# Robot.net
KiCad netlist of a schematic drawn in EAGLE
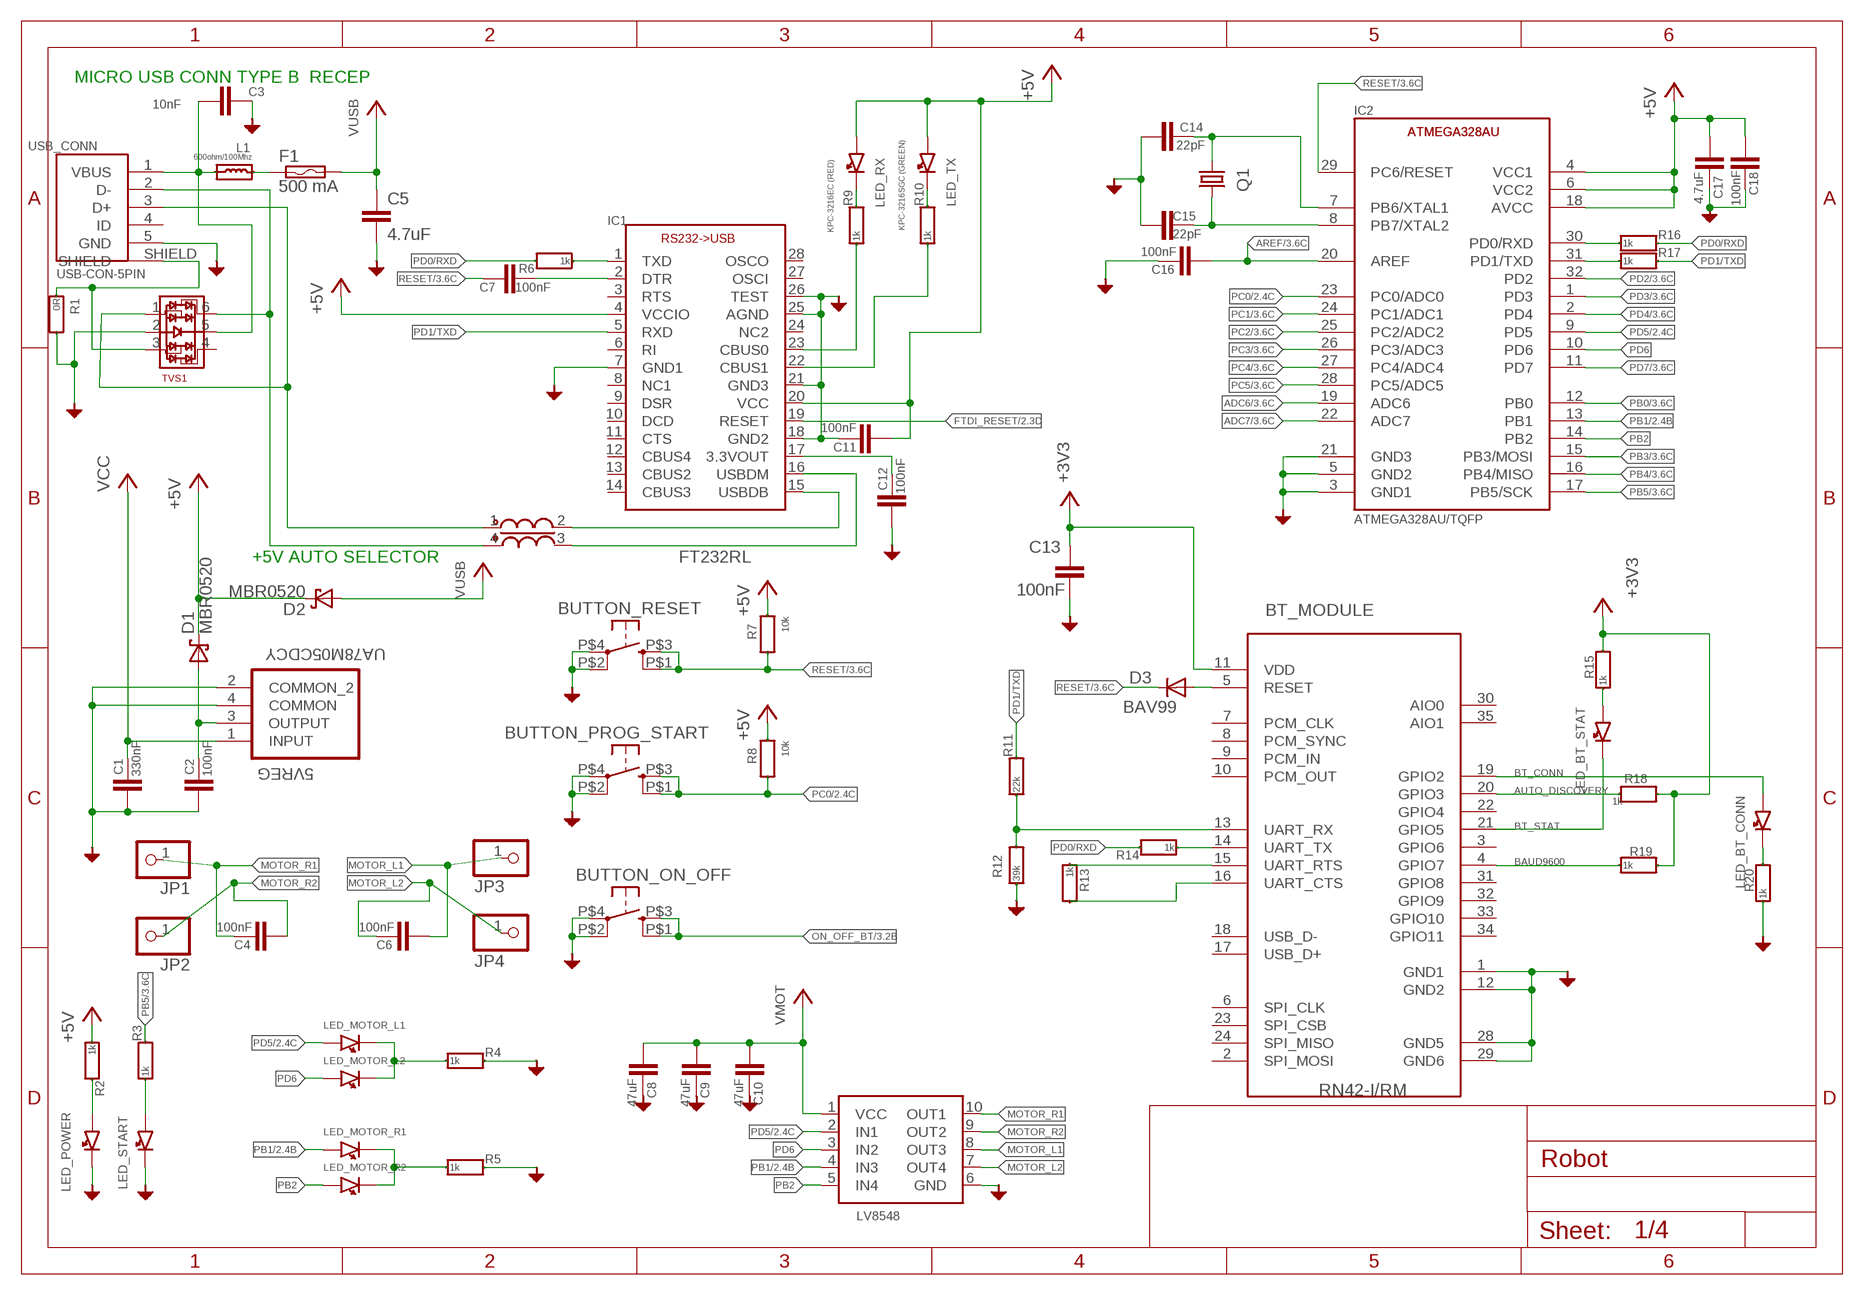
[diagram p0: schematic, sheet 1]
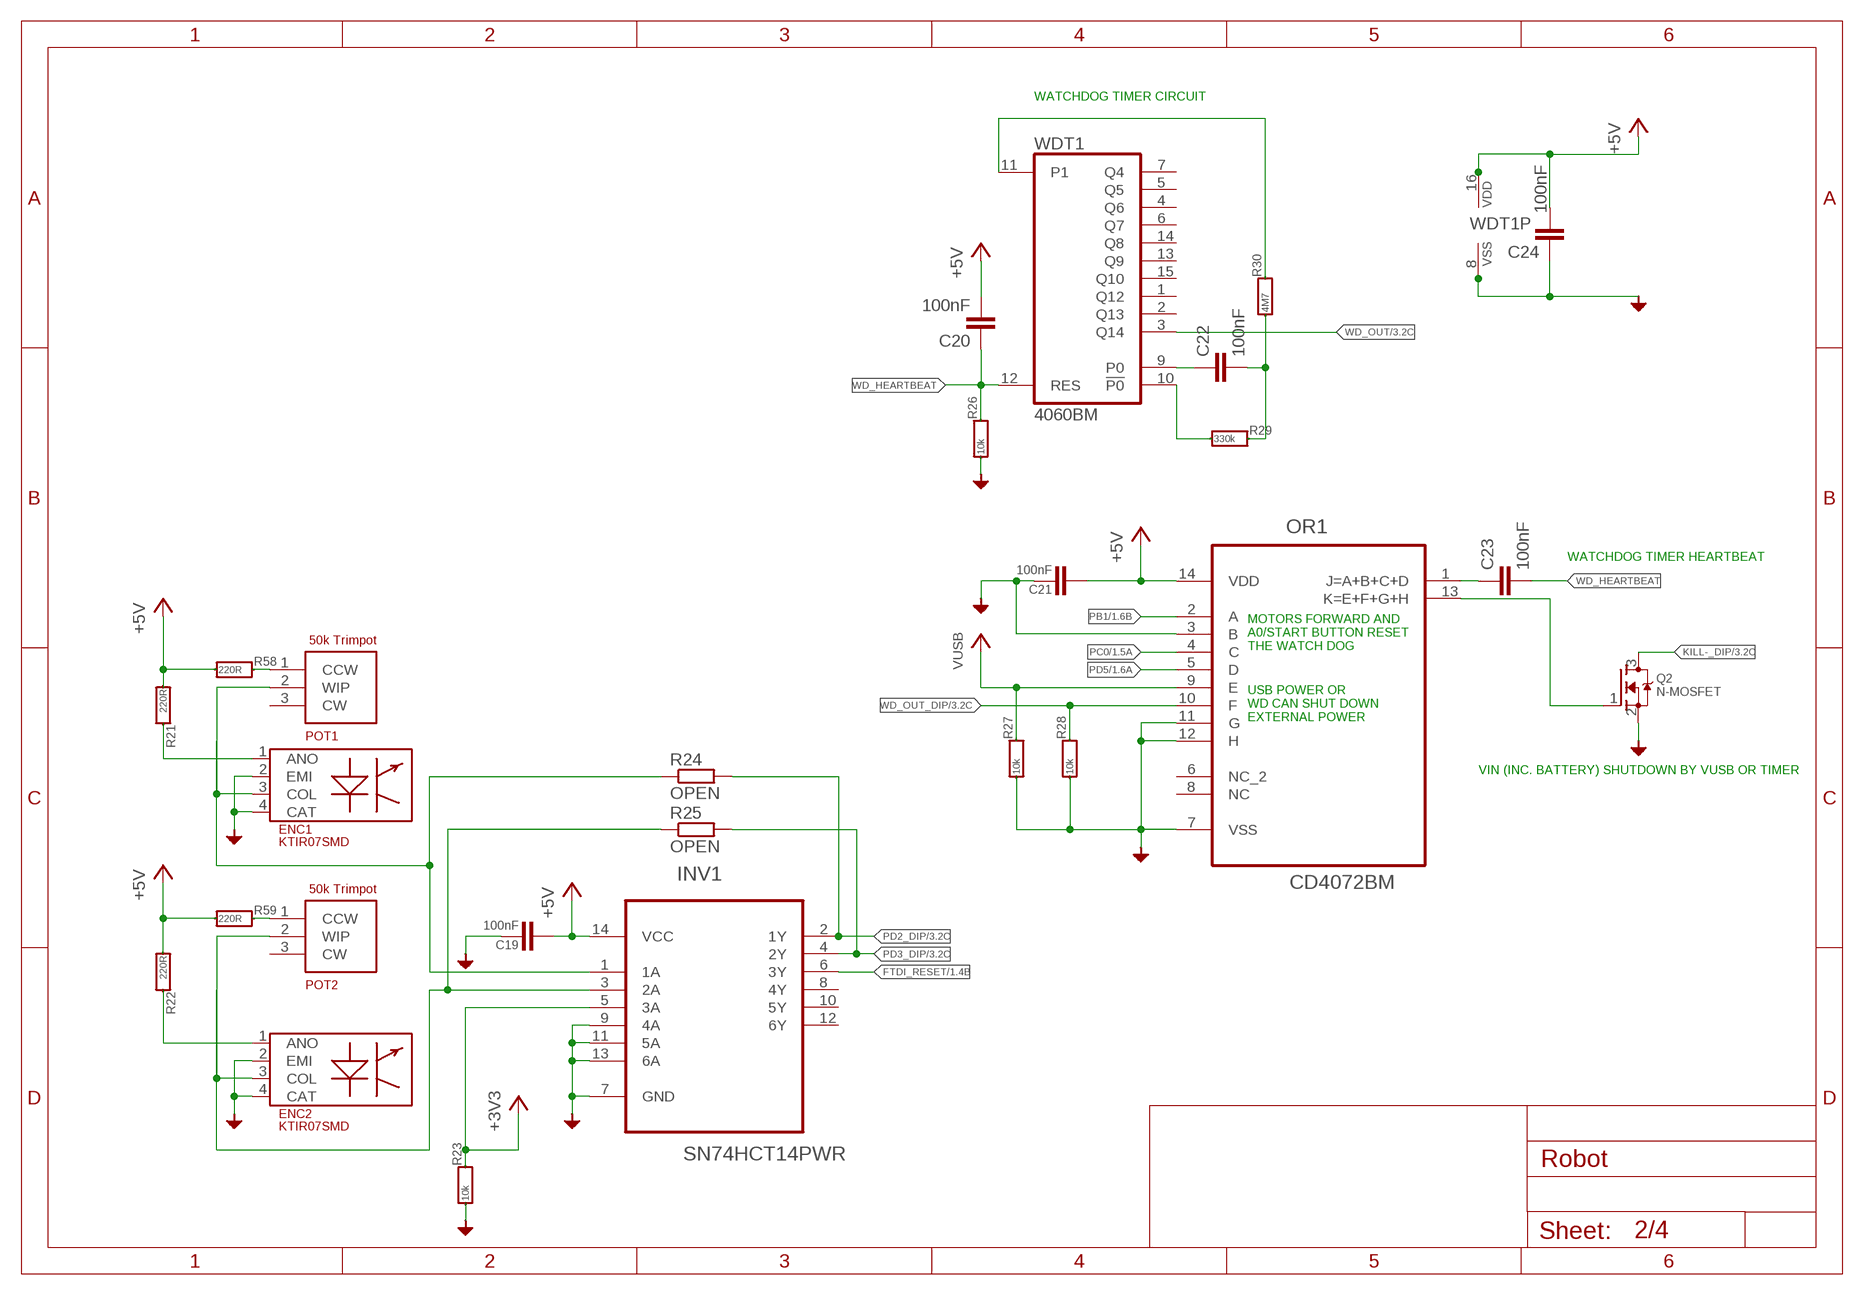
[diagram p1: schematic, sheet 2]
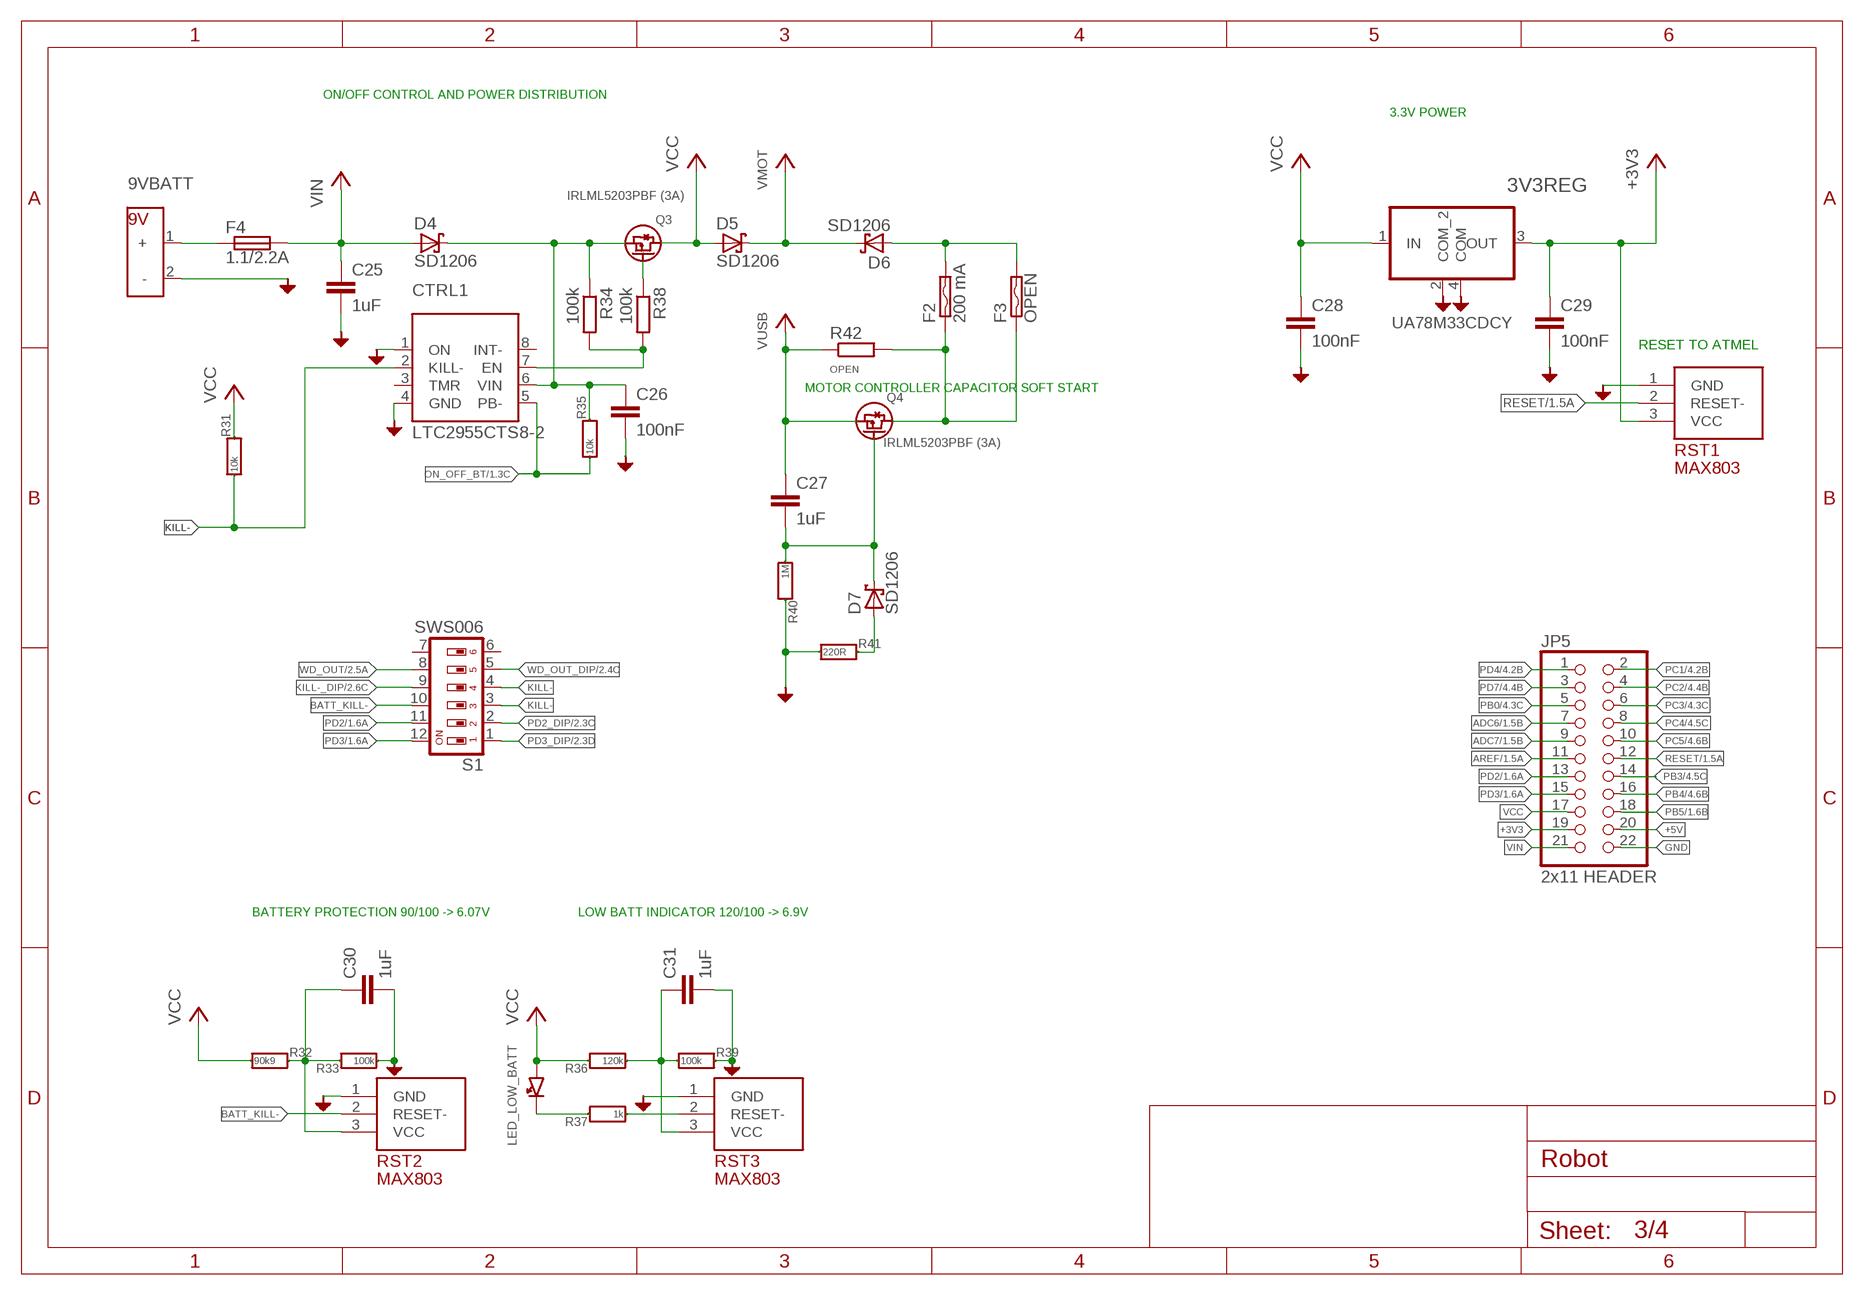
[diagram p2: schematic, sheet 3]
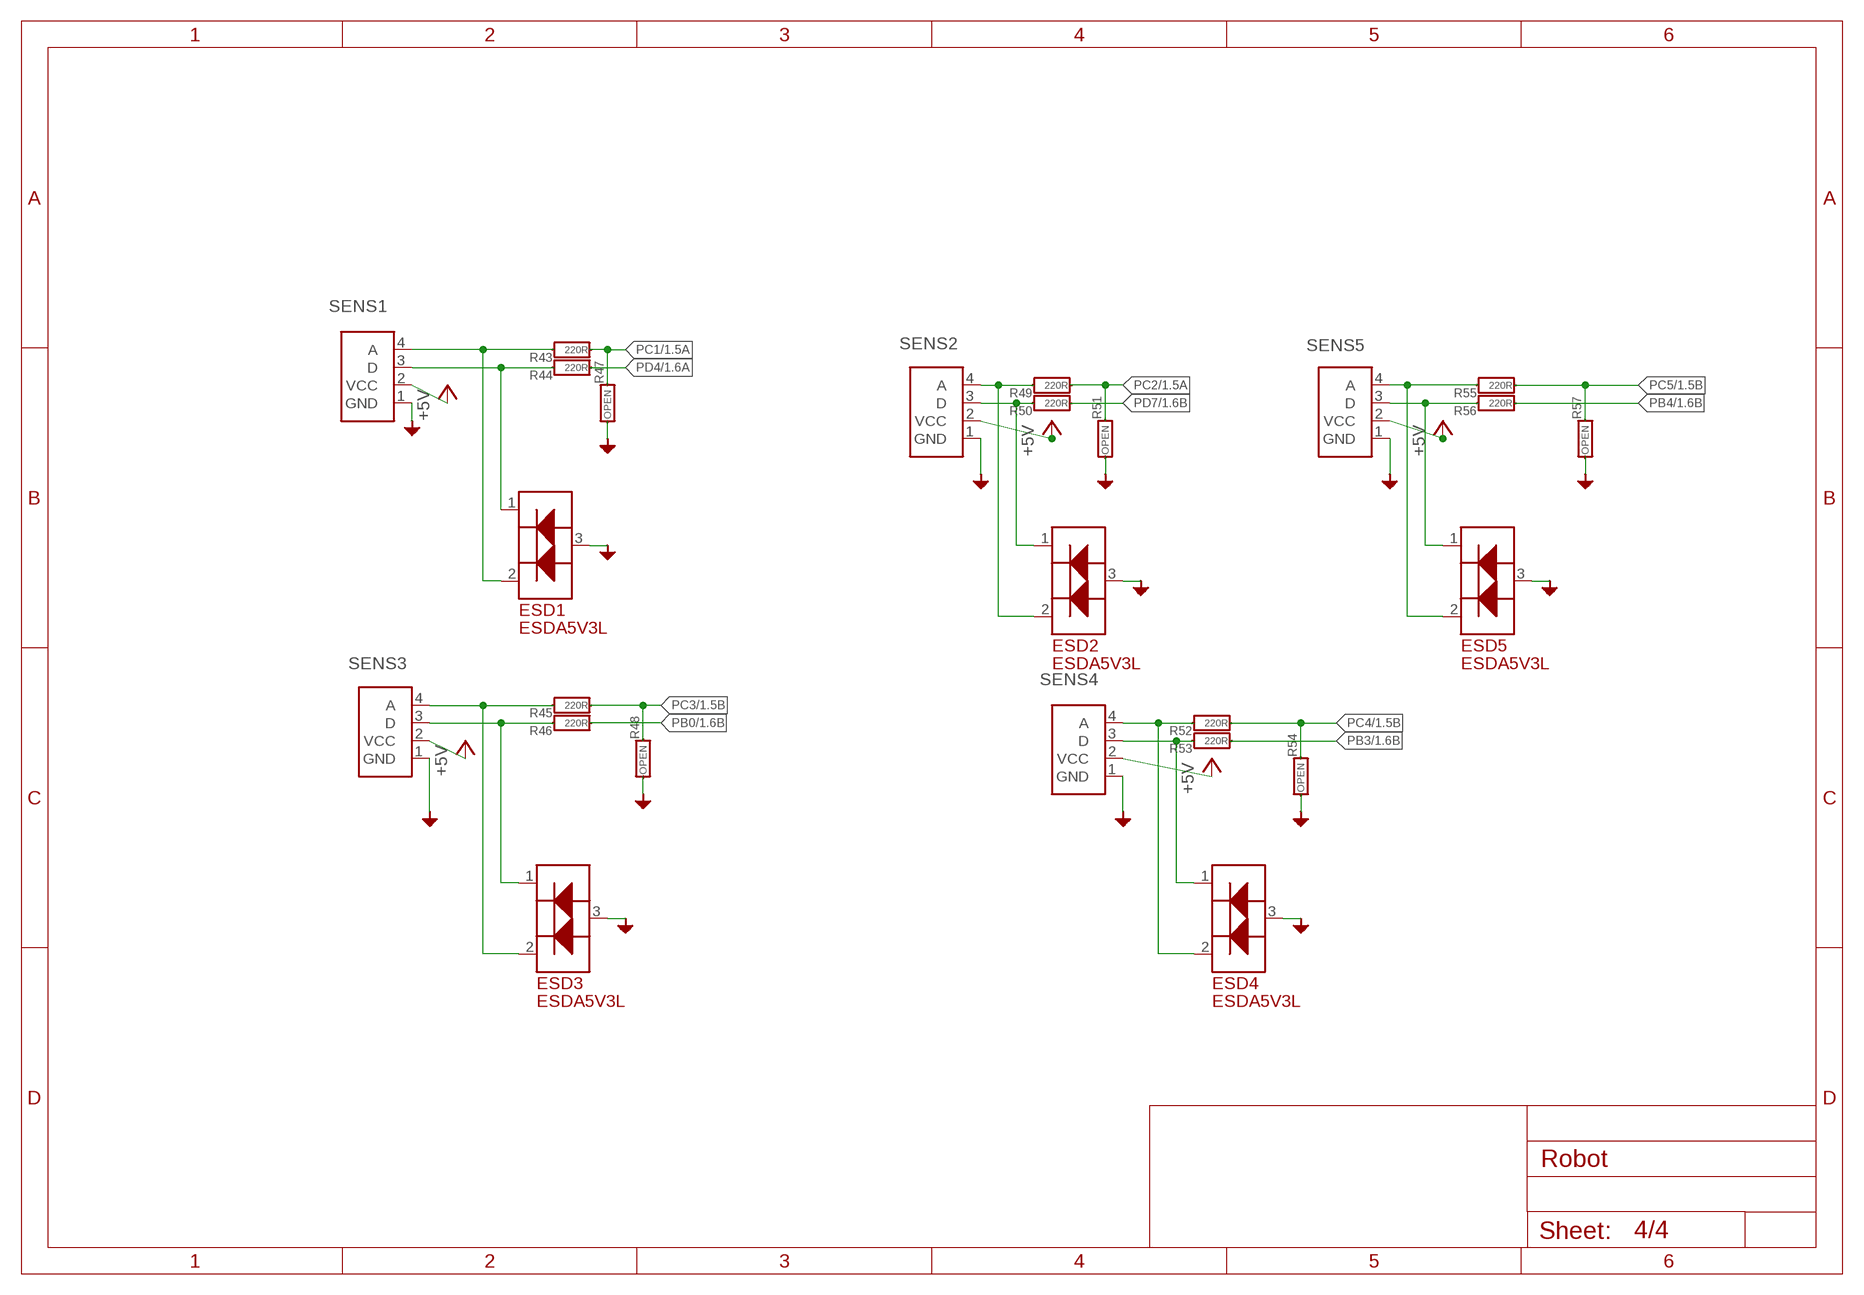
[diagram p3: schematic, sheet 4]

(export (version "E")
  (design (tool "Eeschema 10.0.6"))
  (components
    (comp (ref "C19")
      (value "100nF")
      (footprint "eagle-import:C0805")
      (fields (field (name "MF") "AVX") (field (name "MPN") "08055C104KAT2A"))
      (libsource (lib "eagle-import") (part "C-EUC0805"))
    )
    (comp (ref "C20")
      (value "100nF")
      (footprint "eagle-import:C0805")
      (fields (field (name "MF") "AVX") (field (name "MPN") "08055C104KAT2A"))
      (libsource (lib "eagle-import") (part "C-EUC0805"))
    )
    (comp (ref "C21")
      (value "100nF")
      (footprint "eagle-import:C0805")
      (fields (field (name "MF") "AVX") (field (name "MPN") "08055C104KAT2A"))
      (libsource (lib "eagle-import") (part "C-EUC0805"))
    )
    (comp (ref "C22")
      (value "100nF")
      (footprint "eagle-import:C0805")
      (fields (field (name "MF") "AVX") (field (name "MPN") "08055C104KAT2A"))
      (libsource (lib "eagle-import") (part "C-EUC0805"))
    )
    (comp (ref "C23")
      (value "100nF")
      (footprint "eagle-import:C0805")
      (fields (field (name "MF") "AVX") (field (name "MPN") "08055C104KAT2A"))
      (libsource (lib "eagle-import") (part "C-EUC0805"))
    )
    (comp (ref "C24")
      (value "100nF")
      (footprint "eagle-import:C0805")
      (fields (field (name "MF") "AVX") (field (name "MPN") "08055C104KAT2A"))
      (libsource (lib "eagle-import") (part "C-EUC0805"))
    )
    (comp (ref "ENC1")
      (value "KTIR07SMD")
      (footprint "eagle-import:KTIR07")
      (fields (field (name "MF") "KINGBRIGHT") (field (name "MPN") "KTIR0711S"))
      (libsource (lib "eagle-import") (part "KTIR07SMD"))
    )
    (comp (ref "ENC2")
      (value "KTIR07SMD")
      (footprint "eagle-import:KTIR07")
      (fields (field (name "MF") "KINGBRIGHT") (field (name "MPN") "KTIR0711S"))
      (libsource (lib "eagle-import") (part "KTIR07SMD"))
    )
    (comp (ref "INV1")
      (value "SN74HCT14PWR")
      (footprint "eagle-import:SOP65P640X120-14N")
      (fields
        (field (name "MF") "NXP")
        (field (name "MPN") "74HCT14PW,118")
        (field (name "OC_FARNELL") "2438727")
      )
      (libsource (lib "eagle-import") (part "SN74HCT14PWR"))
    )
    (comp (ref "OR1")
      (value "CD4072BM")
      (footprint "eagle-import:SOIC127P600X175-14N")
      (fields (field (name "MF") "TEXAS INSTRUMENTS"))
      (libsource (lib "eagle-import") (part "CD4072BM"))
    )
    (comp (ref "POT1")
      (value "TC33-TRIMPOT")
      (footprint "eagle-import:TC33-TRIMPOT")
      (fields (field (name "MF") "BOURNS") (field (name "MPN") "TC33X-2-503E"))
      (libsource (lib "eagle-import") (part "TC33-TRIMPOT"))
    )
    (comp (ref "POT2")
      (value "TC33-TRIMPOT")
      (footprint "eagle-import:TC33-TRIMPOT")
      (fields (field (name "MF") "BOURNS") (field (name "MPN") "TC33X-2-503E"))
      (libsource (lib "eagle-import") (part "TC33-TRIMPOT"))
    )
    (comp (ref "Q2")
      (value "N-MOSFET")
      (footprint "eagle-import:SOT23")
      (fields (field (name "MF") "FAIRCHILD SEMICONDUCTOR") (field (name "MPN") "FDV301N"))
      (libsource (lib "eagle-import") (part "MOSFET-NREFLOW"))
    )
    (comp (ref "R21")
      (value "220R")
      (footprint "eagle-import:R0805")
      (fields (field (name "MF") "MULTICOMP") (field (name "MPN") "MCWR08X2200FTL"))
      (libsource (lib "eagle-import") (part "MYRES_0805"))
    )
    (comp (ref "R22")
      (value "220R")
      (footprint "eagle-import:R0805")
      (fields (field (name "MF") "MULTICOMP") (field (name "MPN") "MCWR08X2200FTL"))
      (libsource (lib "eagle-import") (part "MYRES_0805"))
    )
    (comp (ref "R23")
      (value "10k")
      (footprint "eagle-import:R0805")
      (fields (field (name "MF") "YAGEO (PHYCOMP)") (field (name "MPN") "RC0805FR-0710KL"))
      (libsource (lib "eagle-import") (part "MYRES_0805"))
    )
    (comp (ref "R24")
      (value "OPEN")
      (footprint "eagle-import:R0805")
      (libsource (lib "eagle-import") (part "R-EU_R0805"))
    )
    (comp (ref "R25")
      (value "OPEN")
      (footprint "eagle-import:R0805")
      (libsource (lib "eagle-import") (part "R-EU_R0805"))
    )
    (comp (ref "R26")
      (value "10k")
      (footprint "eagle-import:R0805")
      (fields (field (name "MF") "YAGEO (PHYCOMP)") (field (name "MPN") "RC0805FR-0710KL"))
      (libsource (lib "eagle-import") (part "MYRES_0805"))
    )
    (comp (ref "R27")
      (value "10k")
      (footprint "eagle-import:R0805")
      (fields (field (name "MF") "YAGEO (PHYCOMP)") (field (name "MPN") "RC0805FR-0710KL"))
      (libsource (lib "eagle-import") (part "MYRES_0805"))
    )
    (comp (ref "R28")
      (value "10k")
      (footprint "eagle-import:R0805")
      (fields (field (name "MF") "YAGEO (PHYCOMP)") (field (name "MPN") "RC0805FR-0710KL"))
      (libsource (lib "eagle-import") (part "MYRES_0805"))
    )
    (comp (ref "R29")
      (value "330k")
      (footprint "eagle-import:R0805")
      (fields (field (name "MF") "VISHAY DRALORIC") (field (name "MPN") "CRCW0805330KFKEA"))
      (libsource (lib "eagle-import") (part "MYRES_0805"))
    )
    (comp (ref "R30")
      (value "4M7")
      (footprint "eagle-import:R0805")
      (fields (field (name "MF") "VISHAY DRALORIC") (field (name "MPN") "RCV08054M70FKEA"))
      (libsource (lib "eagle-import") (part "MYRES_0805"))
    )
    (comp (ref "R58")
      (value "220R")
      (footprint "eagle-import:R0805")
      (fields (field (name "MF") "MULTICOMP") (field (name "MPN") "MCWR08X2200FTL"))
      (libsource (lib "eagle-import") (part "MYRES_0805"))
    )
    (comp (ref "R59")
      (value "220R")
      (footprint "eagle-import:R0805")
      (fields (field (name "MF") "MULTICOMP") (field (name "MPN") "MCWR08X2200FTL"))
      (libsource (lib "eagle-import") (part "MYRES_0805"))
    )
    (comp (ref "WDT1")
      (value "4060BM")
      (footprint "eagle-import:SO16")
      (fields
        (field (name "MF") "TEXAS INSTRUMENTS")
        (field (name "MPN") "CD4060BM")
        (field (name "OC_FARNELL") "1741260")
      )
      (libsource (lib "eagle-import") (part "4060D"))
    )
    (comp (ref "5VREG")
      (value "UA78M05CDCY")
      (footprint "eagle-import:SOT230P700X180-4N")
      (fields (field (name "MF") "TEXAS INSTRUMENTS") (field (name "OC_FARNELL") "2296030"))
      (libsource (lib "eagle-import") (part "UA78M05CDCY"))
    )
    (comp (ref "BT_MODULE")
      (value "RN42-I/RM")
      (footprint "eagle-import:RN42")
      (fields (field (name "MF") "MICROCHIP"))
      (libsource (lib "eagle-import") (part "BLUETOOTH-RN42{dblquote}"))
    )
    (comp (ref "BUTTON_ON_OFF")
      (value "KSC921J")
      (footprint "eagle-import:TACT_SWITCH_4_PIN")
      (fields (field (name "MF") "C & K COMPONENTS") (field (name "MPN") "KSC921J LFS"))
      (libsource (lib "eagle-import") (part "KSC921J"))
    )
    (comp (ref "BUTTON_PROG_START")
      (value "KSC921J")
      (footprint "eagle-import:TACT_SWITCH_4_PIN")
      (fields (field (name "MF") "C & K COMPONENTS") (field (name "MPN") "KSC921J LFS"))
      (libsource (lib "eagle-import") (part "KSC921J"))
    )
    (comp (ref "BUTTON_RESET")
      (value "KSC921J")
      (footprint "eagle-import:TACT_SWITCH_4_PIN")
      (fields (field (name "MF") "C & K COMPONENTS") (field (name "MPN") "KSC921J LFS"))
      (libsource (lib "eagle-import") (part "KSC921J"))
    )
    (comp (ref "C1")
      (value "330nF")
      (footprint "eagle-import:C0805")
      (fields (field (name "MF") "AVX") (field (name "MPN") "08053C334KAT2A"))
      (libsource (lib "eagle-import") (part "C-EUC0805"))
    )
    (comp (ref "C2")
      (value "100nF")
      (footprint "eagle-import:C0805")
      (fields (field (name "MF") "AVX") (field (name "MPN") "08055C104KAT2A"))
      (libsource (lib "eagle-import") (part "C-EUC0805"))
    )
    (comp (ref "C3")
      (value "10nF")
      (footprint "eagle-import:C0805")
      (fields (field (name "MF") "MULTICOMP") (field (name "MPN") "MC0805B103K500CT"))
      (libsource (lib "eagle-import") (part "C-EUC0805"))
    )
    (comp (ref "C4")
      (value "100nF")
      (footprint "eagle-import:C0805")
      (fields (field (name "MF") "AVX") (field (name "MPN") "08055C104KAT2A"))
      (libsource (lib "eagle-import") (part "C-EUC0805"))
    )
    (comp (ref "C5")
      (value "4.7uF")
      (footprint "eagle-import:C0805")
      (fields (field (name "MF") "MURATA") (field (name "MPN") "GRM21BR61E475KA12L"))
      (libsource (lib "eagle-import") (part "C-EUC0805"))
    )
    (comp (ref "C6")
      (value "100nF")
      (footprint "eagle-import:C0805")
      (fields (field (name "MF") "AVX") (field (name "MPN") "08055C104KAT2A"))
      (libsource (lib "eagle-import") (part "C-EUC0805"))
    )
    (comp (ref "C7")
      (value "100nF")
      (footprint "eagle-import:C0805")
      (fields (field (name "MF") "AVX") (field (name "MPN") "08055C104KAT2A"))
      (libsource (lib "eagle-import") (part "C-EUC0805"))
    )
    (comp (ref "C8")
      (value "47uF")
      (footprint "eagle-import:C1210")
      (fields (field (name "MF") "MURATA") (field (name "MPN") "GRM32EC81C476KE15L"))
      (libsource (lib "eagle-import") (part "C-EUC1210"))
    )
    (comp (ref "C9")
      (value "47uF")
      (footprint "eagle-import:C1210")
      (fields (field (name "MF") "MURATA") (field (name "MPN") "GRM32EC81C476KE15L"))
      (libsource (lib "eagle-import") (part "C-EUC1210"))
    )
    (comp (ref "C10")
      (value "47uF")
      (footprint "eagle-import:C1210")
      (fields (field (name "MF") "MURATA") (field (name "MPN") "GRM32EC81C476KE15L"))
      (libsource (lib "eagle-import") (part "C-EUC1210"))
    )
    (comp (ref "C11")
      (value "100nF")
      (footprint "eagle-import:C0805")
      (fields (field (name "MF") "AVX") (field (name "MPN") "08055C104KAT2A"))
      (libsource (lib "eagle-import") (part "C-EUC0805"))
    )
    (comp (ref "C12")
      (value "100nF")
      (footprint "eagle-import:C0805")
      (fields (field (name "MF") "AVX") (field (name "MPN") "08055C104KAT2A"))
      (libsource (lib "eagle-import") (part "C-EUC0805"))
    )
    (comp (ref "C13")
      (value "100nF")
      (footprint "eagle-import:C0805")
      (fields (field (name "MF") "AVX") (field (name "MPN") "08055C104KAT2A"))
      (libsource (lib "eagle-import") (part "resistor_C-EUC0805"))
    )
    (comp (ref "C14")
      (value "22pF")
      (footprint "eagle-import:C0805")
      (fields (field (name "MF") "YAGEO (PHYCOMP)") (field (name "MPN") "CC0805JRNPO9BN220"))
      (libsource (lib "eagle-import") (part "C-EUC0805"))
    )
    (comp (ref "C15")
      (value "22pF")
      (footprint "eagle-import:C0805")
      (fields (field (name "MF") "YAGEO (PHYCOMP)") (field (name "MPN") "CC0805JRNPO9BN220"))
      (libsource (lib "eagle-import") (part "C-EUC0805"))
    )
    (comp (ref "C16")
      (value "100nF")
      (footprint "eagle-import:C0805")
      (fields (field (name "MF") "AVX") (field (name "MPN") "08055C104KAT2A"))
      (libsource (lib "eagle-import") (part "C-EUC0805"))
    )
    (comp (ref "C17")
      (value "4.7uF")
      (footprint "eagle-import:C0805")
      (fields (field (name "MF") "MURATA") (field (name "MPN") "GRM21BR61E475KA12L"))
      (libsource (lib "eagle-import") (part "C-EUC0805"))
    )
    (comp (ref "C18")
      (value "100nF")
      (footprint "eagle-import:C0805")
      (fields (field (name "MF") "AVX") (field (name "MPN") "08055C104KAT2A"))
      (libsource (lib "eagle-import") (part "C-EUC0805"))
    )
    (comp (ref "D1")
      (value "MBR0520")
      (footprint "eagle-import:SOD123")
      (fields (field (name "MF") "FAIRCHILD SEMICONDUCTOR") (field (name "MPN") "MBR0520L"))
      (libsource (lib "eagle-import") (part "MBR0520"))
    )
    (comp (ref "D2")
      (value "MBR0520")
      (footprint "eagle-import:SOD123")
      (fields (field (name "MF") "FAIRCHILD SEMICONDUCTOR") (field (name "MPN") "MBR0520L"))
      (libsource (lib "eagle-import") (part "MBR0520"))
    )
    (comp (ref "D3")
      (value "BAV99")
      (footprint "eagle-import:SOT23")
      (fields (field (name "MF") "MULTICOMP"))
      (libsource (lib "eagle-import") (part "D-A1-C3"))
    )
    (comp (ref "F1")
      (value "500 mA")
      (footprint "eagle-import:PT1206")
      (fields (field (name "MF") "TE CONNECTIVITY / RAYCHEM") (field (name "MPN") "NANOSMDC050F/13.2-2"))
      (libsource (lib "eagle-import") (part "POLYSWITCH"))
    )
    (comp (ref "IC1")
      (value "FT232RL")
      (footprint "eagle-import:SSOP28")
      (fields (field (name "MF") "FTDI") (field (name "MPN") "FT232RL-REEL"))
      (libsource (lib "eagle-import") (part "FT232RL"))
    )
    (comp (ref "IC2")
      (value "ATMEGA328AU/TQFP")
      (footprint "eagle-import:TQFP32-08")
      (fields (field (name "MF") "ATMEL") (field (name "MPN") "ATMEGA328P-AU"))
      (libsource (lib "eagle-import") (part "ATMEGA328AU"))
    )
    (comp (ref "JP1")
      (value "1X01 PIN")
      (footprint "eagle-import:1X01")
      (fields (field (name "MF") "WURTH ELEKTRONIK") (field (name "MPN") "61300111121"))
      (libsource (lib "eagle-import") (part "PINHD-1X1"))
    )
    (comp (ref "JP2")
      (value "1X01 PIN")
      (footprint "eagle-import:1X01")
      (fields (field (name "MF") "WURTH ELEKTRONIK") (field (name "MPN") "61300111121"))
      (libsource (lib "eagle-import") (part "PINHD-1X1"))
    )
    (comp (ref "JP3")
      (value "1X01 PIN")
      (footprint "eagle-import:1X01")
      (fields (field (name "MF") "WURTH ELEKTRONIK") (field (name "MPN") "61300111121"))
      (libsource (lib "eagle-import") (part "PINHD-1X1"))
    )
    (comp (ref "JP4")
      (value "1X01 PIN")
      (footprint "eagle-import:1X01")
      (fields (field (name "MF") "WURTH ELEKTRONIK") (field (name "MPN") "61300111121"))
      (libsource (lib "eagle-import") (part "PINHD-1X1"))
    )
    (comp (ref "L1")
      (value "600ohm/100Mhz")
      (footprint "eagle-import:R0603")
      (fields (field (name "MF") "WURTH ELEKTRONIK") (field (name "MPN") "742792651"))
      (libsource (lib "eagle-import") (part "INDUCTOR_0603_600R"))
    )
    (comp (ref "LED_BT_CONN")
      (value "KPC-3216SGC")
      (footprint "eagle-import:LED3216_PAC")
      (fields (field (name "MF") "KINGBRIGHT"))
      (libsource (lib "eagle-import") (part "SMDLED_3216"))
    )
    (comp (ref "LED_BT_STAT")
      (value "KPC-3216SGC")
      (footprint "eagle-import:LED3216_PAC")
      (fields (field (name "MF") "KINGBRIGHT"))
      (libsource (lib "eagle-import") (part "SMDLED_3216"))
    )
    (comp (ref "LED_MOTOR_L1")
      (value "APT3216QBC/D (BLUE)")
      (footprint "eagle-import:LED3216_PAC")
      (fields
        (field (name "MF") "KINGBRIGHT")
        (field (name "MOUSER_PART_NO") "604-APT3216QBC/D")
        (field (name "MPN") "KP-3216QBC-D")
      )
      (libsource (lib "eagle-import") (part "SMDLED_3216"))
    )
    (comp (ref "LED_MOTOR_L2")
      (value "KPC-3216YC")
      (footprint "eagle-import:LED3216_PAC")
      (fields (field (name "MF") "KINGBRIGHT"))
      (libsource (lib "eagle-import") (part "SMDLED_3216"))
    )
    (comp (ref "LED_MOTOR_R1")
      (value "APT3216QBC/D (BLUE)")
      (footprint "eagle-import:LED3216_PAC")
      (fields
        (field (name "MF") "KINGBRIGHT")
        (field (name "MOUSER_PART_NO") "604-APT3216QBC/D")
        (field (name "MPN") "KP-3216QBC-D")
      )
      (libsource (lib "eagle-import") (part "SMDLED_3216"))
    )
    (comp (ref "LED_MOTOR_R2")
      (value "KPC-3216YC")
      (footprint "eagle-import:LED3216_PAC")
      (fields (field (name "MF") "KINGBRIGHT"))
      (libsource (lib "eagle-import") (part "SMDLED_3216"))
    )
    (comp (ref "LED_POWER")
      (value "KPC-3216SGC (GREEN)")
      (footprint "eagle-import:LED3216_PAC")
      (fields (field (name "MF") "KINGBRIGHT") (field (name "MPN") "KPC-3216SGC"))
      (libsource (lib "eagle-import") (part "SMDLED_3216"))
    )
    (comp (ref "LED_RX")
      (value "KPC-3216EC (RED)")
      (footprint "eagle-import:LED3216_PAC")
      (fields (field (name "MF") "KINGBRIGHT") (field (name "MPN") "KPC-3216EC"))
      (libsource (lib "eagle-import") (part "SMDLED_3216"))
    )
    (comp (ref "LED_START")
      (value "KPC-3216SGC")
      (footprint "eagle-import:LED3216_PAC")
      (fields (field (name "MF") "KINGBRIGHT"))
      (libsource (lib "eagle-import") (part "SMDLED_3216"))
    )
    (comp (ref "LED_TX")
      (value "KPC-3216SGC (GREEN)")
      (footprint "eagle-import:LED3216_PAC")
      (fields (field (name "MF") "KINGBRIGHT") (field (name "MPN") "KPC-3216SGC"))
      (libsource (lib "eagle-import") (part "SMDLED_3216"))
    )
    (comp (ref "MOTOR_CONTROLLER")
      (value "LV8548")
      (footprint "eagle-import:LV8548")
      (fields (field (name "MF") "ON SEMICONDUCTOR") (field (name "MPN") "LV8548MC-AH"))
      (libsource (lib "eagle-import") (part "LV8548"))
    )
    (comp (ref "Q1")
      (value "16MHz")
      (footprint "eagle-import:SM49")
      (fields
        (field (name "MF") "IQD FREQUENCY PRODUCTS")
        (field (name "MPN") "LFXTAL003237")
        (field (name "OC_FARNELL") "9713808")
      )
      (libsource (lib "eagle-import") (part "CRYSTALSM49"))
    )
    (comp (ref "R1")
      (value "0R")
      (footprint "eagle-import:R0805")
      (fields (field (name "MF") "MULTICOMP") (field (name "MPN") "MC01W08050R"))
      (libsource (lib "eagle-import") (part "MYRES_0805"))
    )
    (comp (ref "R2")
      (value "1k")
      (footprint "eagle-import:R0805")
      (fields (field (name "MF") "VISHAY DRALORIC") (field (name "MPN") "CRCW08051K00FKTA"))
      (libsource (lib "eagle-import") (part "MYRES_0805"))
    )
    (comp (ref "R3")
      (value "1k")
      (footprint "eagle-import:R0805")
      (fields (field (name "MF") "VISHAY DRALORIC") (field (name "MPN") "CRCW08051K00FKTA"))
      (libsource (lib "eagle-import") (part "MYRES_0805"))
    )
    (comp (ref "R4")
      (value "1k")
      (footprint "eagle-import:R0805")
      (fields (field (name "MF") "VISHAY DRALORIC") (field (name "MPN") "CRCW08051K00FKTA"))
      (libsource (lib "eagle-import") (part "MYRES_0805"))
    )
    (comp (ref "R5")
      (value "1k")
      (footprint "eagle-import:R0805")
      (fields (field (name "MF") "VISHAY DRALORIC") (field (name "MPN") "CRCW08051K00FKTA"))
      (libsource (lib "eagle-import") (part "MYRES_0805"))
    )
    (comp (ref "R6")
      (value "1k")
      (footprint "eagle-import:R0805")
      (fields (field (name "MF") "VISHAY DRALORIC") (field (name "MPN") "CRCW08051K00FKTA"))
      (libsource (lib "eagle-import") (part "MYRES_0805"))
    )
    (comp (ref "R7")
      (value "10k")
      (footprint "eagle-import:R0805")
      (fields (field (name "MF") "YAGEO (PHYCOMP)") (field (name "MPN") "RC0805FR-0710KL"))
      (libsource (lib "eagle-import") (part "MYRES_0805"))
    )
    (comp (ref "R8")
      (value "10k")
      (footprint "eagle-import:R0805")
      (fields (field (name "MF") "YAGEO (PHYCOMP)") (field (name "MPN") "RC0805FR-0710KL"))
      (libsource (lib "eagle-import") (part "MYRES_0805"))
    )
    (comp (ref "R9")
      (value "1k")
      (footprint "eagle-import:R0805")
      (fields (field (name "MF") "VISHAY DRALORIC") (field (name "MPN") "CRCW08051K00FKTA"))
      (libsource (lib "eagle-import") (part "MYRES_0805"))
    )
    (comp (ref "R10")
      (value "1k")
      (footprint "eagle-import:R0805")
      (fields (field (name "MF") "VISHAY DRALORIC") (field (name "MPN") "CRCW08051K00FKTA"))
      (libsource (lib "eagle-import") (part "MYRES_0805"))
    )
    (comp (ref "R11")
      (value "22k")
      (footprint "eagle-import:R0805")
      (fields (field (name "MF") "WELWYN") (field (name "MPN") "WCR0805-22KFI"))
      (libsource (lib "eagle-import") (part "MYRES_0805"))
    )
    (comp (ref "R12")
      (value "39k")
      (footprint "eagle-import:R0805")
      (fields (field (name "MF") "WELWYN") (field (name "MPN") "WCR0805-39KFI"))
      (libsource (lib "eagle-import") (part "MYRES_0805"))
    )
    (comp (ref "R13")
      (value "1k")
      (footprint "eagle-import:R0805")
      (fields (field (name "MF") "VISHAY DRALORIC") (field (name "MPN") "CRCW08051K00FKTA"))
      (libsource (lib "eagle-import") (part "MYRES_0805"))
    )
    (comp (ref "R14")
      (value "1k")
      (footprint "eagle-import:R0805")
      (fields (field (name "MF") "VISHAY DRALORIC") (field (name "MPN") "CRCW08051K00FKTA"))
      (libsource (lib "eagle-import") (part "MYRES_0805"))
    )
    (comp (ref "R15")
      (value "1k")
      (footprint "eagle-import:R0805")
      (fields (field (name "MF") "VISHAY DRALORIC") (field (name "MPN") "CRCW08051K00FKTA"))
      (libsource (lib "eagle-import") (part "MYRES_0805"))
    )
    (comp (ref "R16")
      (value "1k")
      (footprint "eagle-import:R0805")
      (fields (field (name "MF") "VISHAY DRALORIC") (field (name "MPN") "CRCW08051K00FKTA"))
      (libsource (lib "eagle-import") (part "MYRES_0805"))
    )
    (comp (ref "R17")
      (value "1k")
      (footprint "eagle-import:R0805")
      (fields (field (name "MF") "VISHAY DRALORIC") (field (name "MPN") "CRCW08051K00FKTA"))
      (libsource (lib "eagle-import") (part "MYRES_0805"))
    )
    (comp (ref "R18")
      (value "1k")
      (footprint "eagle-import:R0805")
      (fields (field (name "MF") "VISHAY DRALORIC") (field (name "MPN") "CRCW08051K00FKTA"))
      (libsource (lib "eagle-import") (part "MYRES_0805"))
    )
    (comp (ref "R19")
      (value "1k")
      (footprint "eagle-import:R0805")
      (fields (field (name "MF") "VISHAY DRALORIC") (field (name "MPN") "CRCW08051K00FKTA"))
      (libsource (lib "eagle-import") (part "MYRES_0805"))
    )
    (comp (ref "R20")
      (value "1k")
      (footprint "eagle-import:R0805")
      (fields (field (name "MF") "VISHAY DRALORIC") (field (name "MPN") "CRCW08051K00FKTA"))
      (libsource (lib "eagle-import") (part "MYRES_0805"))
    )
    (comp (ref "TVS1")
      (value "PRTR5V0U4Y")
      (footprint "eagle-import:SOT363")
      (fields (field (name "MF") "NXP") (field (name "MPN") "PRTR5V0U4Y,125"))
      (libsource (lib "eagle-import") (part "PRTR5V0U4Y"))
    )
    (comp (ref "USB_CONN")
      (value "USB-CON-5PIN")
      (footprint "eagle-import:USB-MICRO-MOLEX-105017-0001_V2")
      (fields (field (name "MF") "MOLEX") (field (name "MPN") "105017-0001"))
      (libsource (lib "eagle-import") (part "USB-CON-5PIN"))
    )
    (comp (ref "USB_FILTER")
      (value "SRF3216A")
      (footprint "eagle-import:SRF3216A")
      (fields (field (name "MF") "BOURNS") (field (name "MPN") "SRF3216A-900Y"))
      (libsource (lib "eagle-import") (part "SRF3216A"))
    )
    (comp (ref "ESD1")
      (value "ESDA5V3L")
      (footprint "eagle-import:SOT23")
      (fields (field (name "MF") "STMICROELECTRONICS"))
      (libsource (lib "eagle-import") (part "ESDA5V3L"))
    )
    (comp (ref "ESD2")
      (value "ESDA5V3L")
      (footprint "eagle-import:SOT23")
      (fields (field (name "MF") "STMICROELECTRONICS"))
      (libsource (lib "eagle-import") (part "ESDA5V3L"))
    )
    (comp (ref "ESD3")
      (value "ESDA5V3L")
      (footprint "eagle-import:SOT23")
      (fields (field (name "MF") "STMICROELECTRONICS"))
      (libsource (lib "eagle-import") (part "ESDA5V3L"))
    )
    (comp (ref "ESD4")
      (value "ESDA5V3L")
      (footprint "eagle-import:SOT23")
      (fields (field (name "MF") "STMICROELECTRONICS"))
      (libsource (lib "eagle-import") (part "ESDA5V3L"))
    )
    (comp (ref "ESD5")
      (value "ESDA5V3L")
      (footprint "eagle-import:SOT23")
      (fields (field (name "MF") "STMICROELECTRONICS"))
      (libsource (lib "eagle-import") (part "ESDA5V3L"))
    )
    (comp (ref "R43")
      (value "220R")
      (footprint "eagle-import:R0805")
      (fields (field (name "MF") "MULTICOMP") (field (name "MPN") "MCWR08X2200FTL"))
      (libsource (lib "eagle-import") (part "MYRES_0805"))
    )
    (comp (ref "R44")
      (value "220R")
      (footprint "eagle-import:R0805")
      (fields (field (name "MF") "MULTICOMP") (field (name "MPN") "MCWR08X2200FTL"))
      (libsource (lib "eagle-import") (part "MYRES_0805"))
    )
    (comp (ref "R45")
      (value "220R")
      (footprint "eagle-import:R0805")
      (fields (field (name "MF") "MULTICOMP") (field (name "MPN") "MCWR08X2200FTL"))
      (libsource (lib "eagle-import") (part "MYRES_0805"))
    )
    (comp (ref "R46")
      (value "220R")
      (footprint "eagle-import:R0805")
      (fields (field (name "MF") "MULTICOMP") (field (name "MPN") "MCWR08X2200FTL"))
      (libsource (lib "eagle-import") (part "MYRES_0805"))
    )
    (comp (ref "R47")
      (value "OPEN")
      (footprint "eagle-import:R0805")
      (libsource (lib "eagle-import") (part "MYRES_0805"))
    )
    (comp (ref "R48")
      (value "OPEN")
      (footprint "eagle-import:R0805")
      (libsource (lib "eagle-import") (part "MYRES_0805"))
    )
    (comp (ref "R49")
      (value "220R")
      (footprint "eagle-import:R0805")
      (fields (field (name "MF") "MULTICOMP") (field (name "MPN") "MCWR08X2200FTL"))
      (libsource (lib "eagle-import") (part "MYRES_0805"))
    )
    (comp (ref "R50")
      (value "220R")
      (footprint "eagle-import:R0805")
      (fields (field (name "MF") "MULTICOMP") (field (name "MPN") "MCWR08X2200FTL"))
      (libsource (lib "eagle-import") (part "MYRES_0805"))
    )
    (comp (ref "R51")
      (value "OPEN")
      (footprint "eagle-import:R0805")
      (libsource (lib "eagle-import") (part "MYRES_0805"))
    )
    (comp (ref "R52")
      (value "220R")
      (footprint "eagle-import:R0805")
      (fields (field (name "MF") "MULTICOMP") (field (name "MPN") "MCWR08X2200FTL"))
      (libsource (lib "eagle-import") (part "MYRES_0805"))
    )
    (comp (ref "R53")
      (value "220R")
      (footprint "eagle-import:R0805")
      (fields (field (name "MF") "MULTICOMP") (field (name "MPN") "MCWR08X2200FTL"))
      (libsource (lib "eagle-import") (part "MYRES_0805"))
    )
    (comp (ref "R54")
      (value "OPEN")
      (footprint "eagle-import:R0805")
      (libsource (lib "eagle-import") (part "MYRES_0805"))
    )
    (comp (ref "R55")
      (value "220R")
      (footprint "eagle-import:R0805")
      (fields (field (name "MF") "MULTICOMP") (field (name "MPN") "MCWR08X2200FTL"))
      (libsource (lib "eagle-import") (part "MYRES_0805"))
    )
    (comp (ref "R56")
      (value "220R")
      (footprint "eagle-import:R0805")
      (fields (field (name "MF") "MULTICOMP") (field (name "MPN") "MCWR08X2200FTL"))
      (libsource (lib "eagle-import") (part "MYRES_0805"))
    )
    (comp (ref "R57")
      (value "OPEN")
      (footprint "eagle-import:R0805")
      (libsource (lib "eagle-import") (part "MYRES_0805"))
    )
    (comp (ref "SENS1")
      (value "ROBOT_SENSOR")
      (footprint "eagle-import:ROBOT_SENSOR")
      (libsource (lib "eagle-import") (part "ROBOT_SENSOR"))
    )
    (comp (ref "SENS2")
      (value "ROBOT_SENSOR")
      (footprint "eagle-import:ROBOT_SENSOR")
      (libsource (lib "eagle-import") (part "ROBOT_SENSOR"))
    )
    (comp (ref "SENS3")
      (value "ROBOT_SENSOR")
      (footprint "eagle-import:ROBOT_SENSOR")
      (libsource (lib "eagle-import") (part "ROBOT_SENSOR"))
    )
    (comp (ref "SENS4")
      (value "ROBOT_SENSOR")
      (footprint "eagle-import:ROBOT_SENSOR")
      (libsource (lib "eagle-import") (part "ROBOT_SENSOR"))
    )
    (comp (ref "SENS5")
      (value "ROBOT_SENSOR")
      (footprint "eagle-import:ROBOT_SENSOR")
      (libsource (lib "eagle-import") (part "ROBOT_SENSOR"))
    )
    (comp (ref "3V3REG")
      (value "UA78M33CDCY")
      (footprint "eagle-import:SOT230P700X180-4N")
      (fields (field (name "MF") "TEXAS INSTRUMENTS") (field (name "OC_FARNELL") "2296031"))
      (libsource (lib "eagle-import") (part "UA78M33CDCY"))
    )
    (comp (ref "9VBATT")
      (value "BATTERY_9V")
      (footprint "eagle-import:BATTERY_PAC")
      (fields (field (name "MF") "KEYSTONE") (field (name "MPN") "967"))
      (libsource (lib "eagle-import") (part "BATTERY_9V"))
    )
    (comp (ref "C25")
      (value "1uF")
      (footprint "eagle-import:C0805")
      (fields (field (name "MF") "WALSIN") (field (name "MPN") "0805B104K500CT"))
      (libsource (lib "eagle-import") (part "C-EUC0805"))
    )
    (comp (ref "C26")
      (value "100nF")
      (footprint "eagle-import:C0805")
      (fields (field (name "MF") "AVX") (field (name "MPN") "08055C104KAT2A"))
      (libsource (lib "eagle-import") (part "C-EUC0805"))
    )
    (comp (ref "C27")
      (value "1uF")
      (footprint "eagle-import:C0805")
      (fields (field (name "MF") "WALSIN") (field (name "MPN") "0805B104K500CT"))
      (libsource (lib "eagle-import") (part "C-EUC0805"))
    )
    (comp (ref "C28")
      (value "100nF")
      (footprint "eagle-import:C0805")
      (fields (field (name "MF") "AVX") (field (name "MPN") "08055C104KAT2A"))
      (libsource (lib "eagle-import") (part "C-EUC0805"))
    )
    (comp (ref "C29")
      (value "100nF")
      (footprint "eagle-import:C0805")
      (fields (field (name "MF") "AVX") (field (name "MPN") "08055C104KAT2A"))
      (libsource (lib "eagle-import") (part "C-EUC0805"))
    )
    (comp (ref "C30")
      (value "1uF")
      (footprint "eagle-import:C0805")
      (fields (field (name "MF") "WALSIN") (field (name "MPN") "0805B104K500CT"))
      (libsource (lib "eagle-import") (part "C-EUC0805"))
    )
    (comp (ref "C31")
      (value "1uF")
      (footprint "eagle-import:C0805")
      (fields (field (name "MF") "WALSIN") (field (name "MPN") "0805B104K500CT"))
      (libsource (lib "eagle-import") (part "C-EUC0805"))
    )
    (comp (ref "CTRL1")
      (value "LTC2955CTS8-2")
      (footprint "eagle-import:8TSOT23")
      (fields (field (name "MF") "LINEAR TECHNOLOGY") (field (name "MPN") "LTC2955CTS8-2#TRMPBF"))
      (libsource (lib "eagle-import") (part "LTC2955CTS8-2"))
    )
    (comp (ref "D4")
      (value "SD1206")
      (footprint "eagle-import:SD1206")
      (fields (field (name "MF") "AVX") (field (name "MPN") "SD1206S040S2R0"))
      (libsource (lib "eagle-import") (part "SD1206"))
    )
    (comp (ref "D5")
      (value "SD1206")
      (footprint "eagle-import:SD1206")
      (fields (field (name "MF") "AVX") (field (name "MPN") "SD1206S040S2R0"))
      (libsource (lib "eagle-import") (part "SD1206"))
    )
    (comp (ref "D6")
      (value "SD1206")
      (footprint "eagle-import:SD1206")
      (fields (field (name "MF") "AVX") (field (name "MPN") "SD1206S040S2R0"))
      (libsource (lib "eagle-import") (part "SD1206"))
    )
    (comp (ref "D7")
      (value "SD1206")
      (footprint "eagle-import:SD1206")
      (fields (field (name "MF") "AVX") (field (name "MPN") "SD1206S040S2R0"))
      (libsource (lib "eagle-import") (part "SD1206"))
    )
    (comp (ref "F2")
      (value "200 mA")
      (footprint "eagle-import:PT1206")
      (fields (field (name "MF") "TE CONNECTIVITY / RAYCHEM") (field (name "MPN") "NANOSMDC020F-2"))
      (libsource (lib "eagle-import") (part "POLYSWITCH"))
    )
    (comp (ref "F3")
      (value "OPEN")
      (footprint "eagle-import:PT1206")
      (libsource (lib "eagle-import") (part "POLYSWITCH"))
    )
    (comp (ref "F4")
      (value "1.1/2.2A")
      (footprint "eagle-import:C1812")
      (fields (field (name "MF") "TE CONNECTIVITY / RAYCHEM") (field (name "MPN") "MINISMDC110F/16-2"))
      (libsource (lib "eagle-import") (part "POLYSWITCH_1812C1812"))
    )
    (comp (ref "JP5")
      (value "2x11 HEADER")
      (footprint "eagle-import:2X11")
      (fields (field (name "MF") "MULTICOMP") (field (name "MPN") "2214S-22SG-85"))
      (libsource (lib "eagle-import") (part "PINHD-2X11"))
    )
    (comp (ref "LED_LOW_BATT")
      (value "KPC-3216EC (RED)")
      (footprint "eagle-import:LED3216_PAC")
      (fields (field (name "MF") "KINGBRIGHT") (field (name "MPN") "KPC-3216EC"))
      (libsource (lib "eagle-import") (part "SMDLED_3216"))
    )
    (comp (ref "Q3")
      (value "IRLML5203PBF (3A)")
      (footprint "eagle-import:SOT23")
      (fields (field (name "MF") "INTERNATIONAL RECTIFIER") (field (name "MPN") "IRLML5203PBF"))
      (libsource (lib "eagle-import") (part "PFET"))
    )
    (comp (ref "Q4")
      (value "IRLML5203PBF (3A)")
      (footprint "eagle-import:SOT23")
      (fields (field (name "MF") "INTERNATIONAL RECTIFIER") (field (name "MPN") "IRLML5203PBF"))
      (libsource (lib "eagle-import") (part "PFET"))
    )
    (comp (ref "R31")
      (value "10k")
      (footprint "eagle-import:R0805")
      (fields (field (name "MF") "YAGEO (PHYCOMP)") (field (name "MPN") "RC0805FR-0710KL"))
      (libsource (lib "eagle-import") (part "MYRES_0805"))
    )
    (comp (ref "R32")
      (value "90k9")
      (footprint "eagle-import:R0805")
      (fields (field (name "MF") "MULTICOMP") (field (name "MPN") "MC01W0805190K9"))
      (libsource (lib "eagle-import") (part "MYRES_0805"))
    )
    (comp (ref "R33")
      (value "100k")
      (footprint "eagle-import:R0805")
      (fields (field (name "MF") "YAGEO (PHYCOMP)") (field (name "MPN") "RC0805FR-07100KL"))
      (libsource (lib "eagle-import") (part "MYRES_0805"))
    )
    (comp (ref "R34")
      (value "100k")
      (footprint "eagle-import:R0805")
      (fields (field (name "MF") "YAGEO (PHYCOMP)") (field (name "MPN") "RC0805FR-07100KL"))
      (libsource (lib "eagle-import") (part "R-EU_R0805"))
    )
    (comp (ref "R35")
      (value "10k")
      (footprint "eagle-import:R0805")
      (fields (field (name "MF") "YAGEO (PHYCOMP)") (field (name "MPN") "RC0805FR-0710KL"))
      (libsource (lib "eagle-import") (part "MYRES_0805"))
    )
    (comp (ref "R36")
      (value "120k")
      (footprint "eagle-import:R0805")
      (fields (field (name "MF") "YAGEO (PHYCOMP)") (field (name "MPN") "RC0805FR-07120KL"))
      (libsource (lib "eagle-import") (part "MYRES_0805"))
    )
    (comp (ref "R37")
      (value "1k")
      (footprint "eagle-import:R0805")
      (fields (field (name "MF") "VISHAY DRALORIC") (field (name "MPN") "CRCW08051K00FKTA"))
      (libsource (lib "eagle-import") (part "MYRES_0805"))
    )
    (comp (ref "R38")
      (value "100k")
      (footprint "eagle-import:R0805")
      (fields (field (name "MF") "YAGEO (PHYCOMP)") (field (name "MPN") "RC0805FR-07100KL"))
      (libsource (lib "eagle-import") (part "R-EU_R0805"))
    )
    (comp (ref "R39")
      (value "100k")
      (footprint "eagle-import:R0805")
      (fields (field (name "MF") "YAGEO (PHYCOMP)") (field (name "MPN") "RC0805FR-07100KL"))
      (libsource (lib "eagle-import") (part "MYRES_0805"))
    )
    (comp (ref "R40")
      (value "1M")
      (footprint "eagle-import:R0805")
      (fields (field (name "MF") "VISHAY DALE") (field (name "MPN") "CRCW08051M00FKTB"))
      (libsource (lib "eagle-import") (part "MYRES_0805"))
    )
    (comp (ref "R41")
      (value "220R")
      (footprint "eagle-import:R0805")
      (fields (field (name "MF") "MULTICOMP") (field (name "MPN") "MCWR08X2200FTL"))
      (libsource (lib "eagle-import") (part "MYRES_0805"))
    )
    (comp (ref "R42")
      (value "OPEN")
      (footprint "eagle-import:R0603")
      (libsource (lib "eagle-import") (part "R-EU_R0603"))
    )
    (comp (ref "RST1")
      (value "MAX803SC")
      (footprint "eagle-import:SC70-3L")
      (fields (field (name "MF") "ON SEMICONDUCTOR") (field (name "MPN") "MAX803SQ293T1G"))
      (libsource (lib "eagle-import") (part "MAX803SC"))
    )
    (comp (ref "RST2")
      (value "MAX803SC")
      (footprint "eagle-import:SC70-3L")
      (fields (field (name "MF") "ON SEMICONDUCTOR") (field (name "MPN") "MAX803SQ293T1G"))
      (libsource (lib "eagle-import") (part "MAX803SC"))
    )
    (comp (ref "RST3")
      (value "MAX803SC")
      (footprint "eagle-import:SC70-3L")
      (fields (field (name "MF") "ON SEMICONDUCTOR") (field (name "MPN") "MAX803SQ293T1G"))
      (libsource (lib "eagle-import") (part "MAX803SC"))
    )
    (comp (ref "S1")
      (value "SWS006")
      (footprint "eagle-import:SMS-006")
      (fields (field (name "MF") "MULTICOMP") (field (name "MPN") "MCDM(R)-06-T"))
      (libsource (lib "eagle-import") (part "SWS006"))
    )
  )
  (nets
    (net (code "1") (name "+3V3") (class "Default")
      (node (ref "3V3REG") (pin "3") (pinfunction "OUT_3") (pintype "output"))
      (node (ref "BT_MODULE") (pin "11") (pinfunction "VDD_11") (pintype "bidirectional"))
      (node (ref "C13") (pin "1") (pinfunction "1_1") (pintype "passive"))
      (node (ref "C29") (pin "1") (pinfunction "1_1") (pintype "passive"))
      (node (ref "INV1") (pin "5") (pinfunction "3A_5") (pintype "input"))
      (node (ref "JP5") (pin "19") (pinfunction "19_19") (pintype "passive"))
      (node (ref "R15") (pin "2") (pinfunction "P$2_2") (pintype "bidirectional"))
      (node (ref "R18") (pin "2") (pinfunction "P$2_2") (pintype "bidirectional"))
      (node (ref "R19") (pin "2") (pinfunction "P$2_2") (pintype "bidirectional"))
      (node (ref "R23") (pin "2") (pinfunction "P$2_2") (pintype "bidirectional"))
      (node (ref "RST1") (pin "3") (pinfunction "VCC_3") (pintype "bidirectional"))
    )
    (net (code "2") (name "+5V") (class "Default")
      (node (ref "C11") (pin "2") (pinfunction "2_2") (pintype "passive"))
      (node (ref "C17") (pin "2") (pinfunction "2_2") (pintype "passive"))
      (node (ref "C18") (pin "2") (pinfunction "2_2") (pintype "passive"))
      (node (ref "C19") (pin "2") (pinfunction "2_2") (pintype "passive"))
      (node (ref "C20") (pin "2") (pinfunction "2_2") (pintype "passive"))
      (node (ref "C21") (pin "2") (pinfunction "2_2") (pintype "passive"))
      (node (ref "C24") (pin "2") (pinfunction "2_2") (pintype "passive"))
      (node (ref "D1") (pin "1") (pinfunction "K_1") (pintype "passive"))
      (node (ref "D2") (pin "1") (pinfunction "K_1") (pintype "passive"))
      (node (ref "IC1") (pin "20") (pinfunction "VCC_20") (pintype "bidirectional"))
      (node (ref "IC1") (pin "4") (pinfunction "VCCIO_4") (pintype "bidirectional"))
      (node (ref "IC2") (pin "18") (pinfunction "AVCC_18") (pintype "bidirectional"))
      (node (ref "IC2") (pin "4") (pinfunction "VCC1_4") (pintype "bidirectional"))
      (node (ref "IC2") (pin "6") (pinfunction "VCC2_6") (pintype "bidirectional"))
      (node (ref "INV1") (pin "14") (pinfunction "VCC_14") (pintype "power_in"))
      (node (ref "JP5") (pin "20") (pinfunction "20_20") (pintype "passive"))
      (node (ref "LED_RX") (pin "1") (pinfunction "1_1") (pintype "bidirectional"))
      (node (ref "LED_TX") (pin "1") (pinfunction "1_1") (pintype "bidirectional"))
      (node (ref "OR1") (pin "14") (pinfunction "VDD_14") (pintype "power_in"))
      (node (ref "R2") (pin "1") (pinfunction "P$1_1") (pintype "bidirectional"))
      (node (ref "R21") (pin "1") (pinfunction "P$1_1") (pintype "bidirectional"))
      (node (ref "R22") (pin "1") (pinfunction "P$1_1") (pintype "bidirectional"))
      (node (ref "R58") (pin "1") (pinfunction "P$1_1") (pintype "bidirectional"))
      (node (ref "R59") (pin "1") (pinfunction "P$1_1") (pintype "bidirectional"))
      (node (ref "R7") (pin "2") (pinfunction "P$2_2") (pintype "bidirectional"))
      (node (ref "R8") (pin "2") (pinfunction "P$2_2") (pintype "bidirectional"))
      (node (ref "SENS1") (pin "2") (pinfunction "VCC_2") (pintype "bidirectional"))
      (node (ref "SENS2") (pin "2") (pinfunction "VCC_2") (pintype "bidirectional"))
      (node (ref "SENS3") (pin "2") (pinfunction "VCC_2") (pintype "bidirectional"))
      (node (ref "SENS4") (pin "2") (pinfunction "VCC_2") (pintype "bidirectional"))
      (node (ref "SENS5") (pin "2") (pinfunction "VCC_2") (pintype "bidirectional"))
      (node (ref "WDT1") (pin "16") (pinfunction "VDD_16") (pintype "power_in"))
    )
    (net (code "3") (name "ADC6") (class "Default")
      (node (ref "IC2") (pin "19") (pinfunction "ADC6_19") (pintype "bidirectional"))
      (node (ref "JP5") (pin "7") (pinfunction "7_7") (pintype "passive"))
    )
    (net (code "4") (name "ADC7") (class "Default")
      (node (ref "IC2") (pin "22") (pinfunction "ADC7_22") (pintype "bidirectional"))
      (node (ref "JP5") (pin "9") (pinfunction "9_9") (pintype "passive"))
    )
    (net (code "5") (name "AREF") (class "Default")
      (node (ref "C16") (pin "2") (pinfunction "2_2") (pintype "passive"))
      (node (ref "IC2") (pin "20") (pinfunction "AREF_20") (pintype "bidirectional"))
      (node (ref "JP5") (pin "11") (pinfunction "11_11") (pintype "passive"))
    )
    (net (code "6") (name "AUTO_DISCOVERY") (class "Default")
      (node (ref "BT_MODULE") (pin "20") (pinfunction "GPIO3_20") (pintype "bidirectional"))
      (node (ref "R18") (pin "1") (pinfunction "P$1_1") (pintype "bidirectional"))
    )
    (net (code "7") (name "BATT_KILL-") (class "Default")
      (node (ref "RST2") (pin "2") (pinfunction "RESET-_2") (pintype "bidirectional"))
      (node (ref "S1") (pin "10") (pinfunction "10_10") (pintype "passive"))
    )
    (net (code "8") (name "BAUD9600") (class "Default")
      (node (ref "BT_MODULE") (pin "4") (pinfunction "GPIO7_4") (pintype "bidirectional"))
      (node (ref "R19") (pin "1") (pinfunction "P$1_1") (pintype "bidirectional"))
    )
    (net (code "9") (name "BT_CONN") (class "Default")
      (node (ref "BT_MODULE") (pin "19") (pinfunction "GPIO2_19") (pintype "bidirectional"))
      (node (ref "LED_BT_CONN") (pin "1") (pinfunction "1_1") (pintype "bidirectional"))
    )
    (net (code "10") (name "BT_STAT") (class "Default")
      (node (ref "BT_MODULE") (pin "21") (pinfunction "GPIO5_21") (pintype "bidirectional"))
      (node (ref "LED_BT_STAT") (pin "2") (pinfunction "2_2") (pintype "bidirectional"))
    )
    (net (code "11") (name "FTDI_RESET") (class "Default")
      (node (ref "IC1") (pin "19") (pinfunction "RESET_19") (pintype "bidirectional"))
      (node (ref "INV1") (pin "6") (pinfunction "3Y_6") (pintype "output"))
    )
    (net (code "12") (name "GND") (class "Default")
      (node (ref "3V3REG") (pin "2") (pinfunction "COM_2_2") (pintype "passive"))
      (node (ref "3V3REG") (pin "4") (pinfunction "COM_4") (pintype "passive"))
      (node (ref "5VREG") (pin "2") (pinfunction "COMMON_2_2") (pintype "power_in"))
      (node (ref "5VREG") (pin "4") (pinfunction "COMMON_4") (pintype "power_in"))
      (node (ref "9VBATT") (pin "2") (pinfunction "-_2") (pintype "bidirectional"))
      (node (ref "BT_MODULE") (pin "1") (pinfunction "GND1_1") (pintype "bidirectional"))
      (node (ref "BT_MODULE") (pin "12") (pinfunction "GND2_12") (pintype "bidirectional"))
      (node (ref "BT_MODULE") (pin "28") (pinfunction "GND5_28") (pintype "bidirectional"))
      (node (ref "BT_MODULE") (pin "29") (pinfunction "GND6_29") (pintype "bidirectional"))
      (node (ref "BUTTON_ON_OFF") (pin "P$2") (pinfunction "2_P$2") (pintype "passive"))
      (node (ref "BUTTON_ON_OFF") (pin "P$4") (pinfunction "1_P$4") (pintype "passive"))
      (node (ref "BUTTON_PROG_START") (pin "P$2") (pinfunction "2_P$2") (pintype "passive"))
      (node (ref "BUTTON_PROG_START") (pin "P$4") (pinfunction "1_P$4") (pintype "passive"))
      (node (ref "BUTTON_RESET") (pin "P$2") (pinfunction "2_P$2") (pintype "passive"))
      (node (ref "BUTTON_RESET") (pin "P$4") (pinfunction "1_P$4") (pintype "passive"))
      (node (ref "C1") (pin "2") (pinfunction "2_2") (pintype "passive"))
      (node (ref "C10") (pin "1") (pinfunction "1_1") (pintype "passive"))
      (node (ref "C11") (pin "1") (pinfunction "1_1") (pintype "passive"))
      (node (ref "C12") (pin "2") (pinfunction "2_2") (pintype "passive"))
      (node (ref "C13") (pin "2") (pinfunction "2_2") (pintype "passive"))
      (node (ref "C14") (pin "2") (pinfunction "2_2") (pintype "passive"))
      (node (ref "C15") (pin "2") (pinfunction "2_2") (pintype "passive"))
      (node (ref "C16") (pin "1") (pinfunction "1_1") (pintype "passive"))
      (node (ref "C17") (pin "1") (pinfunction "1_1") (pintype "passive"))
      (node (ref "C18") (pin "1") (pinfunction "1_1") (pintype "passive"))
      (node (ref "C19") (pin "1") (pinfunction "1_1") (pintype "passive"))
      (node (ref "C2") (pin "2") (pinfunction "2_2") (pintype "passive"))
      (node (ref "C21") (pin "1") (pinfunction "1_1") (pintype "passive"))
      (node (ref "C24") (pin "1") (pinfunction "1_1") (pintype "passive"))
      (node (ref "C25") (pin "2") (pinfunction "2_2") (pintype "passive"))
      (node (ref "C26") (pin "2") (pinfunction "2_2") (pintype "passive"))
      (node (ref "C28") (pin "2") (pinfunction "2_2") (pintype "passive"))
      (node (ref "C29") (pin "2") (pinfunction "2_2") (pintype "passive"))
      (node (ref "C3") (pin "1") (pinfunction "1_1") (pintype "passive"))
      (node (ref "C30") (pin "2") (pinfunction "2_2") (pintype "passive"))
      (node (ref "C31") (pin "2") (pinfunction "2_2") (pintype "passive"))
      (node (ref "C5") (pin "2") (pinfunction "2_2") (pintype "passive"))
      (node (ref "C8") (pin "1") (pinfunction "1_1") (pintype "passive"))
      (node (ref "C9") (pin "1") (pinfunction "1_1") (pintype "passive"))
      (node (ref "CTRL1") (pin "1") (pinfunction "ON_1") (pintype "bidirectional"))
      (node (ref "CTRL1") (pin "4") (pinfunction "GND_4") (pintype "bidirectional"))
      (node (ref "ENC1") (pin "2") (pinfunction "EMI_2") (pintype "bidirectional"))
      (node (ref "ENC1") (pin "4") (pinfunction "CAT_4") (pintype "bidirectional"))
      (node (ref "ENC2") (pin "2") (pinfunction "EMI_2") (pintype "bidirectional"))
      (node (ref "ENC2") (pin "4") (pinfunction "CAT_4") (pintype "bidirectional"))
      (node (ref "ESD1") (pin "3") (pinfunction "P$3_3") (pintype "bidirectional"))
      (node (ref "ESD2") (pin "3") (pinfunction "P$3_3") (pintype "bidirectional"))
      (node (ref "ESD3") (pin "3") (pinfunction "P$3_3") (pintype "bidirectional"))
      (node (ref "ESD4") (pin "3") (pinfunction "P$3_3") (pintype "bidirectional"))
      (node (ref "ESD5") (pin "3") (pinfunction "P$3_3") (pintype "bidirectional"))
      (node (ref "IC1") (pin "18") (pinfunction "GND2_18") (pintype "bidirectional"))
      (node (ref "IC1") (pin "21") (pinfunction "GND3_21") (pintype "bidirectional"))
      (node (ref "IC1") (pin "25") (pinfunction "AGND_25") (pintype "bidirectional"))
      (node (ref "IC1") (pin "26") (pinfunction "TEST_26") (pintype "bidirectional"))
      (node (ref "IC1") (pin "7") (pinfunction "GND1_7") (pintype "bidirectional"))
      (node (ref "IC2") (pin "21") (pinfunction "GND3_21") (pintype "bidirectional"))
      (node (ref "IC2") (pin "3") (pinfunction "GND1_3") (pintype "bidirectional"))
      (node (ref "IC2") (pin "5") (pinfunction "GND2_5") (pintype "bidirectional"))
      (node (ref "INV1") (pin "11") (pinfunction "5A_11") (pintype "input"))
      (node (ref "INV1") (pin "13") (pinfunction "6A_13") (pintype "input"))
      (node (ref "INV1") (pin "7") (pinfunction "GND_7") (pintype "passive"))
      (node (ref "INV1") (pin "9") (pinfunction "4A_9") (pintype "input"))
      (node (ref "JP5") (pin "22") (pinfunction "22_22") (pintype "passive"))
      (node (ref "LED_POWER") (pin "2") (pinfunction "2_2") (pintype "bidirectional"))
      (node (ref "LED_START") (pin "2") (pinfunction "2_2") (pintype "bidirectional"))
      (node (ref "MOTOR_CONTROLLER") (pin "6") (pinfunction "GND_6") (pintype "bidirectional"))
      (node (ref "OR1") (pin "11") (pinfunction "G_11") (pintype "input"))
      (node (ref "OR1") (pin "12") (pinfunction "H_12") (pintype "input"))
      (node (ref "OR1") (pin "3") (pinfunction "B_3") (pintype "input"))
      (node (ref "OR1") (pin "7") (pinfunction "VSS_7") (pintype "power_in"))
      (node (ref "Q2") (pin "2") (pinfunction "S_2") (pintype "bidirectional"))
      (node (ref "R1") (pin "2") (pinfunction "P$2_2") (pintype "bidirectional"))
      (node (ref "R12") (pin "1") (pinfunction "P$1_1") (pintype "bidirectional"))
      (node (ref "R20") (pin "1") (pinfunction "P$1_1") (pintype "bidirectional"))
      (node (ref "R23") (pin "1") (pinfunction "P$1_1") (pintype "bidirectional"))
      (node (ref "R26") (pin "1") (pinfunction "P$1_1") (pintype "bidirectional"))
      (node (ref "R27") (pin "1") (pinfunction "P$1_1") (pintype "bidirectional"))
      (node (ref "R28") (pin "1") (pinfunction "P$1_1") (pintype "bidirectional"))
      (node (ref "R33") (pin "1") (pinfunction "P$1_1") (pintype "bidirectional"))
      (node (ref "R39") (pin "2") (pinfunction "P$2_2") (pintype "bidirectional"))
      (node (ref "R4") (pin "2") (pinfunction "P$2_2") (pintype "bidirectional"))
      (node (ref "R40") (pin "2") (pinfunction "P$2_2") (pintype "bidirectional"))
      (node (ref "R41") (pin "1") (pinfunction "P$1_1") (pintype "bidirectional"))
      (node (ref "R47") (pin "1") (pinfunction "P$1_1") (pintype "bidirectional"))
      (node (ref "R48") (pin "1") (pinfunction "P$1_1") (pintype "bidirectional"))
      (node (ref "R5") (pin "2") (pinfunction "P$2_2") (pintype "bidirectional"))
      (node (ref "R51") (pin "1") (pinfunction "P$1_1") (pintype "bidirectional"))
      (node (ref "R54") (pin "1") (pinfunction "P$1_1") (pintype "bidirectional"))
      (node (ref "R57") (pin "1") (pinfunction "P$1_1") (pintype "bidirectional"))
      (node (ref "RST1") (pin "1") (pinfunction "GND_1") (pintype "bidirectional"))
      (node (ref "RST2") (pin "1") (pinfunction "GND_1") (pintype "bidirectional"))
      (node (ref "RST3") (pin "1") (pinfunction "GND_1") (pintype "bidirectional"))
      (node (ref "SENS1") (pin "1") (pinfunction "GND_1") (pintype "bidirectional"))
      (node (ref "SENS2") (pin "1") (pinfunction "GND_1") (pintype "bidirectional"))
      (node (ref "SENS3") (pin "1") (pinfunction "GND_1") (pintype "bidirectional"))
      (node (ref "SENS4") (pin "1") (pinfunction "GND_1") (pintype "bidirectional"))
      (node (ref "SENS5") (pin "1") (pinfunction "GND_1") (pintype "bidirectional"))
      (node (ref "TVS1") (pin "2") (pinfunction "P$2_2") (pintype "bidirectional"))
      (node (ref "USB_CONN") (pin "5") (pinfunction "GND_5") (pintype "power_in"))
      (node (ref "WDT1") (pin "8") (pinfunction "VSS_8") (pintype "power_in"))
    )
    (net (code "13") (name "KILL-") (class "Default")
      (node (ref "CTRL1") (pin "2") (pinfunction "KILL-_2") (pintype "bidirectional"))
      (node (ref "R31") (pin "1") (pinfunction "P$1_1") (pintype "bidirectional"))
      (node (ref "S1") (pin "3") (pinfunction "3_3") (pintype "passive"))
      (node (ref "S1") (pin "4") (pinfunction "4_4") (pintype "passive"))
    )
    (net (code "14") (name "KILL-_DIP") (class "Default")
      (node (ref "Q2") (pin "3") (pinfunction "D_3") (pintype "bidirectional"))
      (node (ref "S1") (pin "9") (pinfunction "9_9") (pintype "passive"))
    )
    (net (code "15") (name "MOTOR_L1") (class "Default")
      (node (ref "C6") (pin "2") (pinfunction "2_2") (pintype "passive"))
      (node (ref "JP3") (pin "1") (pinfunction "1_1") (pintype "passive"))
      (node (ref "MOTOR_CONTROLLER") (pin "8") (pinfunction "OUT3_8") (pintype "bidirectional"))
    )
    (net (code "16") (name "MOTOR_L2") (class "Default")
      (node (ref "C6") (pin "1") (pinfunction "1_1") (pintype "passive"))
      (node (ref "JP4") (pin "1") (pinfunction "1_1") (pintype "passive"))
      (node (ref "MOTOR_CONTROLLER") (pin "7") (pinfunction "OUT4_7") (pintype "bidirectional"))
    )
    (net (code "17") (name "MOTOR_R1") (class "Default")
      (node (ref "C4") (pin "1") (pinfunction "1_1") (pintype "passive"))
      (node (ref "JP1") (pin "1") (pinfunction "1_1") (pintype "passive"))
      (node (ref "MOTOR_CONTROLLER") (pin "10") (pinfunction "OUT1_10") (pintype "bidirectional"))
    )
    (net (code "18") (name "MOTOR_R2") (class "Default")
      (node (ref "C4") (pin "2") (pinfunction "2_2") (pintype "passive"))
      (node (ref "JP2") (pin "1") (pinfunction "1_1") (pintype "passive"))
      (node (ref "MOTOR_CONTROLLER") (pin "9") (pinfunction "OUT2_9") (pintype "bidirectional"))
    )
    (net (code "19") (name "Net-(5VREG-OUTPUT)") (class "Default")
      (node (ref "5VREG") (pin "3") (pinfunction "OUTPUT_3") (pintype "power_in"))
      (node (ref "C2") (pin "1") (pinfunction "1_1") (pintype "passive"))
      (node (ref "D1") (pin "2") (pinfunction "A_2") (pintype "passive"))
    )
    (net (code "20") (name "Net-(9VBATT-+)") (class "Default")
      (node (ref "9VBATT") (pin "1") (pinfunction "+_1") (pintype "bidirectional"))
      (node (ref "F4") (pin "2") (pinfunction "2_2") (pintype "passive"))
    )
    (net (code "21") (name "Net-(BT_MODULE-RESET)") (class "Default")
      (node (ref "BT_MODULE") (pin "5") (pinfunction "RESET_5") (pintype "bidirectional"))
      (node (ref "D3") (pin "1") (pinfunction "A_1") (pintype "passive"))
    )
    (net (code "22") (name "Net-(BT_MODULE-UART_CTS)") (class "Default")
      (node (ref "BT_MODULE") (pin "16") (pinfunction "UART_CTS_16") (pintype "bidirectional"))
      (node (ref "R13") (pin "2") (pinfunction "P$2_2") (pintype "bidirectional"))
    )
    (net (code "23") (name "Net-(BT_MODULE-UART_RTS)") (class "Default")
      (node (ref "BT_MODULE") (pin "15") (pinfunction "UART_RTS_15") (pintype "bidirectional"))
      (node (ref "R13") (pin "1") (pinfunction "P$1_1") (pintype "bidirectional"))
    )
    (net (code "24") (name "Net-(BT_MODULE-UART_RX)") (class "Default")
      (node (ref "BT_MODULE") (pin "13") (pinfunction "UART_RX_13") (pintype "bidirectional"))
      (node (ref "R11") (pin "1") (pinfunction "P$1_1") (pintype "bidirectional"))
      (node (ref "R12") (pin "2") (pinfunction "P$2_2") (pintype "bidirectional"))
    )
    (net (code "25") (name "Net-(BT_MODULE-UART_TX)") (class "Default")
      (node (ref "BT_MODULE") (pin "14") (pinfunction "UART_TX_14") (pintype "bidirectional"))
      (node (ref "R14") (pin "1") (pinfunction "P$1_1") (pintype "bidirectional"))
    )
    (net (code "26") (name "Net-(CTRL1-EN)") (class "Default")
      (node (ref "CTRL1") (pin "7") (pinfunction "EN_7") (pintype "bidirectional"))
      (node (ref "R34") (pin "2") (pinfunction "2_2") (pintype "passive"))
      (node (ref "R38") (pin "2") (pinfunction "2_2") (pintype "passive"))
    )
    (net (code "27") (name "Net-(CTRL1-VIN)") (class "Default")
      (node (ref "C26") (pin "1") (pinfunction "1_1") (pintype "passive"))
      (node (ref "CTRL1") (pin "6") (pinfunction "VIN_6") (pintype "bidirectional"))
      (node (ref "D4") (pin "CATHODE") (pinfunction "C_CATHODE") (pintype "passive"))
      (node (ref "Q3") (pin "2") (pinfunction "S_2") (pintype "bidirectional"))
      (node (ref "R34") (pin "1") (pinfunction "1_1") (pintype "passive"))
      (node (ref "R35") (pin "2") (pinfunction "P$2_2") (pintype "bidirectional"))
    )
    (net (code "28") (name "Net-(D6-A)") (class "Default")
      (node (ref "D6") (pin "ANODE") (pinfunction "A_ANODE") (pintype "passive"))
      (node (ref "F2") (pin "2A") (pinfunction "2_2A") (pintype "passive"))
      (node (ref "F2") (pin "2B") (pinfunction "2_2B") (pintype "passive"))
      (node (ref "F3") (pin "2A") (pinfunction "2_2A") (pintype "passive"))
      (node (ref "F3") (pin "2B") (pinfunction "2_2B") (pintype "passive"))
    )
    (net (code "29") (name "Net-(D7-A)") (class "Default")
      (node (ref "D7") (pin "ANODE") (pinfunction "A_ANODE") (pintype "passive"))
      (node (ref "R41") (pin "2") (pinfunction "P$2_2") (pintype "bidirectional"))
    )
    (net (code "30") (name "Net-(D7-C)") (class "Default")
      (node (ref "C27") (pin "2") (pinfunction "2_2") (pintype "passive"))
      (node (ref "D7") (pin "CATHODE") (pinfunction "C_CATHODE") (pintype "passive"))
      (node (ref "Q4") (pin "1") (pinfunction "G_1") (pintype "bidirectional"))
      (node (ref "R40") (pin "1") (pinfunction "P$1_1") (pintype "bidirectional"))
    )
    (net (code "31") (name "Net-(ENC1-ANO)") (class "Default")
      (node (ref "ENC1") (pin "1") (pinfunction "ANO_1") (pintype "bidirectional"))
      (node (ref "R21") (pin "2") (pinfunction "P$2_2") (pintype "bidirectional"))
    )
    (net (code "32") (name "Net-(ENC1-COL)") (class "Default")
      (node (ref "ENC1") (pin "3") (pinfunction "COL_3") (pintype "bidirectional"))
      (node (ref "INV1") (pin "1") (pinfunction "1A_1") (pintype "input"))
      (node (ref "POT1") (pin "2") (pinfunction "WIP_2") (pintype "bidirectional"))
      (node (ref "R24") (pin "1") (pinfunction "1_1") (pintype "passive"))
    )
    (net (code "33") (name "Net-(ENC2-ANO)") (class "Default")
      (node (ref "ENC2") (pin "1") (pinfunction "ANO_1") (pintype "bidirectional"))
      (node (ref "R22") (pin "2") (pinfunction "P$2_2") (pintype "bidirectional"))
    )
    (net (code "34") (name "Net-(ENC2-COL)") (class "Default")
      (node (ref "ENC2") (pin "3") (pinfunction "COL_3") (pintype "bidirectional"))
      (node (ref "INV1") (pin "3") (pinfunction "2A_3") (pintype "input"))
      (node (ref "POT2") (pin "2") (pinfunction "WIP_2") (pintype "bidirectional"))
      (node (ref "R25") (pin "1") (pinfunction "1_1") (pintype "passive"))
    )
    (net (code "35") (name "Net-(ESD1-P$1)") (class "Default")
      (node (ref "ESD1") (pin "1") (pinfunction "P$1_1") (pintype "bidirectional"))
      (node (ref "R44") (pin "2") (pinfunction "P$2_2") (pintype "bidirectional"))
      (node (ref "SENS1") (pin "3") (pinfunction "D_3") (pintype "bidirectional"))
    )
    (net (code "36") (name "Net-(ESD1-P$2)") (class "Default")
      (node (ref "ESD1") (pin "2") (pinfunction "P$2_2") (pintype "bidirectional"))
      (node (ref "R43") (pin "2") (pinfunction "P$2_2") (pintype "bidirectional"))
      (node (ref "SENS1") (pin "4") (pinfunction "A_4") (pintype "bidirectional"))
    )
    (net (code "37") (name "Net-(ESD2-P$1)") (class "Default")
      (node (ref "ESD2") (pin "1") (pinfunction "P$1_1") (pintype "bidirectional"))
      (node (ref "R50") (pin "2") (pinfunction "P$2_2") (pintype "bidirectional"))
      (node (ref "SENS2") (pin "3") (pinfunction "D_3") (pintype "bidirectional"))
    )
    (net (code "38") (name "Net-(ESD2-P$2)") (class "Default")
      (node (ref "ESD2") (pin "2") (pinfunction "P$2_2") (pintype "bidirectional"))
      (node (ref "R49") (pin "2") (pinfunction "P$2_2") (pintype "bidirectional"))
      (node (ref "SENS2") (pin "4") (pinfunction "A_4") (pintype "bidirectional"))
    )
    (net (code "39") (name "Net-(ESD3-P$1)") (class "Default")
      (node (ref "ESD3") (pin "1") (pinfunction "P$1_1") (pintype "bidirectional"))
      (node (ref "R46") (pin "2") (pinfunction "P$2_2") (pintype "bidirectional"))
      (node (ref "SENS3") (pin "3") (pinfunction "D_3") (pintype "bidirectional"))
    )
    (net (code "40") (name "Net-(ESD3-P$2)") (class "Default")
      (node (ref "ESD3") (pin "2") (pinfunction "P$2_2") (pintype "bidirectional"))
      (node (ref "R45") (pin "2") (pinfunction "P$2_2") (pintype "bidirectional"))
      (node (ref "SENS3") (pin "4") (pinfunction "A_4") (pintype "bidirectional"))
    )
    (net (code "41") (name "Net-(ESD4-P$1)") (class "Default")
      (node (ref "ESD4") (pin "1") (pinfunction "P$1_1") (pintype "bidirectional"))
      (node (ref "R53") (pin "2") (pinfunction "P$2_2") (pintype "bidirectional"))
      (node (ref "SENS4") (pin "3") (pinfunction "D_3") (pintype "bidirectional"))
    )
    (net (code "42") (name "Net-(ESD4-P$2)") (class "Default")
      (node (ref "ESD4") (pin "2") (pinfunction "P$2_2") (pintype "bidirectional"))
      (node (ref "R52") (pin "2") (pinfunction "P$2_2") (pintype "bidirectional"))
      (node (ref "SENS4") (pin "4") (pinfunction "A_4") (pintype "bidirectional"))
    )
    (net (code "43") (name "Net-(ESD5-P$1)") (class "Default")
      (node (ref "ESD5") (pin "1") (pinfunction "P$1_1") (pintype "bidirectional"))
      (node (ref "R56") (pin "2") (pinfunction "P$2_2") (pintype "bidirectional"))
      (node (ref "SENS5") (pin "3") (pinfunction "D_3") (pintype "bidirectional"))
    )
    (net (code "44") (name "Net-(ESD5-P$2)") (class "Default")
      (node (ref "ESD5") (pin "2") (pinfunction "P$2_2") (pintype "bidirectional"))
      (node (ref "R55") (pin "2") (pinfunction "P$2_2") (pintype "bidirectional"))
      (node (ref "SENS5") (pin "4") (pinfunction "A_4") (pintype "bidirectional"))
    )
    (net (code "45") (name "Net-(IC1-3.3VOUT)") (class "Default")
      (node (ref "C12") (pin "1") (pinfunction "1_1") (pintype "passive"))
      (node (ref "IC1") (pin "17") (pinfunction "3.3VOUT_17") (pintype "bidirectional"))
    )
    (net (code "46") (name "Net-(IC1-CBUS0)") (class "Default")
      (node (ref "IC1") (pin "23") (pinfunction "CBUS0_23") (pintype "bidirectional"))
      (node (ref "R9") (pin "1") (pinfunction "P$1_1") (pintype "bidirectional"))
    )
    (net (code "47") (name "Net-(IC1-CBUS1)") (class "Default")
      (node (ref "IC1") (pin "22") (pinfunction "CBUS1_22") (pintype "bidirectional"))
      (node (ref "R10") (pin "1") (pinfunction "P$1_1") (pintype "bidirectional"))
    )
    (net (code "48") (name "Net-(IC1-DTR)") (class "Default")
      (node (ref "C7") (pin "1") (pinfunction "1_1") (pintype "passive"))
      (node (ref "IC1") (pin "2") (pinfunction "DTR_2") (pintype "bidirectional"))
    )
    (net (code "49") (name "Net-(IC1-TXD)") (class "Default")
      (node (ref "IC1") (pin "1") (pinfunction "TXD_1") (pintype "bidirectional"))
      (node (ref "R6") (pin "1") (pinfunction "P$1_1") (pintype "bidirectional"))
    )
    (net (code "50") (name "Net-(IC1-USBDB)") (class "Default")
      (node (ref "IC1") (pin "15") (pinfunction "USBDB_15") (pintype "bidirectional"))
      (node (ref "USB_FILTER") (pin "2") (pinfunction "P$2_2") (pintype "bidirectional"))
    )
    (net (code "51") (name "Net-(IC1-USBDM)") (class "Default")
      (node (ref "IC1") (pin "16") (pinfunction "USBDM_16") (pintype "bidirectional"))
      (node (ref "USB_FILTER") (pin "3") (pinfunction "P$3_3") (pintype "bidirectional"))
    )
    (net (code "52") (name "Net-(IC2-PB6{slash}XTAL1)") (class "Default")
      (node (ref "C14") (pin "1") (pinfunction "1_1") (pintype "passive"))
      (node (ref "IC2") (pin "7") (pinfunction "PB6/XTAL1_7") (pintype "bidirectional"))
      (node (ref "Q1") (pin "1") (pinfunction "1_1") (pintype "passive"))
    )
    (net (code "53") (name "Net-(IC2-PB7{slash}XTAL2)") (class "Default")
      (node (ref "C15") (pin "1") (pinfunction "1_1") (pintype "passive"))
      (node (ref "IC2") (pin "8") (pinfunction "PB7/XTAL2_8") (pintype "bidirectional"))
      (node (ref "Q1") (pin "2") (pinfunction "2_2") (pintype "passive"))
    )
    (net (code "54") (name "Net-(IC2-PD0{slash}RXD)") (class "Default")
      (node (ref "IC2") (pin "30") (pinfunction "PD0/RXD_30") (pintype "bidirectional"))
      (node (ref "R16") (pin "1") (pinfunction "P$1_1") (pintype "bidirectional"))
    )
    (net (code "55") (name "Net-(IC2-PD1{slash}TXD)") (class "Default")
      (node (ref "IC2") (pin "31") (pinfunction "PD1/TXD_31") (pintype "bidirectional"))
      (node (ref "R17") (pin "1") (pinfunction "P$1_1") (pintype "bidirectional"))
    )
    (net (code "56") (name "Net-(L1-P$1)") (class "Default")
      (node (ref "F1") (pin "1A") (pinfunction "1_1A") (pintype "passive"))
      (node (ref "F1") (pin "1B") (pinfunction "1_1B") (pintype "passive"))
      (node (ref "L1") (pin "1") (pinfunction "P$1_1") (pintype "passive"))
    )
    (net (code "57") (name "Net-(L1-P$2)") (class "Default")
      (node (ref "C3") (pin "2") (pinfunction "2_2") (pintype "passive"))
      (node (ref "L1") (pin "2") (pinfunction "P$2_2") (pintype "passive"))
      (node (ref "TVS1") (pin "5") (pinfunction "P$5_5") (pintype "bidirectional"))
      (node (ref "USB_CONN") (pin "1") (pinfunction "VBUS_1") (pintype "power_in"))
    )
    (net (code "58") (name "Net-(OR1-J=A+B+C+D)") (class "Default")
      (node (ref "C23") (pin "1") (pinfunction "1_1") (pintype "passive"))
      (node (ref "OR1") (pin "1") (pinfunction "J=A+B+C+D_1") (pintype "output"))
    )
    (net (code "59") (name "Net-(OR1-K=E+F+G+H)") (class "Default")
      (node (ref "OR1") (pin "13") (pinfunction "K=E+F+G+H_13") (pintype "output"))
      (node (ref "Q2") (pin "1") (pinfunction "G_1") (pintype "bidirectional"))
    )
    (net (code "60") (name "Net-(POT1-CCW)") (class "Default")
      (node (ref "POT1") (pin "1") (pinfunction "CCW_1") (pintype "bidirectional"))
      (node (ref "R58") (pin "2") (pinfunction "P$2_2") (pintype "bidirectional"))
    )
    (net (code "61") (name "Net-(POT2-CCW)") (class "Default")
      (node (ref "POT2") (pin "1") (pinfunction "CCW_1") (pintype "bidirectional"))
      (node (ref "R59") (pin "2") (pinfunction "P$2_2") (pintype "bidirectional"))
    )
    (net (code "62") (name "Net-(Q3-G)") (class "Default")
      (node (ref "Q3") (pin "1") (pinfunction "G_1") (pintype "bidirectional"))
      (node (ref "R38") (pin "1") (pinfunction "1_1") (pintype "passive"))
    )
    (net (code "63") (name "Net-(Q4-D)") (class "Default")
      (node (ref "F2") (pin "1A") (pinfunction "1_1A") (pintype "passive"))
      (node (ref "F2") (pin "1B") (pinfunction "1_1B") (pintype "passive"))
      (node (ref "F3") (pin "1A") (pinfunction "1_1A") (pintype "passive"))
      (node (ref "F3") (pin "1B") (pinfunction "1_1B") (pintype "passive"))
      (node (ref "Q4") (pin "3") (pinfunction "D_3") (pintype "bidirectional"))
      (node (ref "R42") (pin "2") (pinfunction "2_2") (pintype "passive"))
    )
    (net (code "64") (name "Net-(R1-P$1)") (class "Default")
      (node (ref "R1") (pin "1") (pinfunction "P$1_1") (pintype "bidirectional"))
      (node (ref "TVS1") (pin "3") (pinfunction "P$3_3") (pintype "bidirectional"))
      (node (ref "USB_CONN") (pin "SHIELD") (pinfunction "SHIELD_SHIELD") (pintype "power_in"))
    )
    (net (code "65") (name "Net-(R2-P$2)") (class "Default")
      (node (ref "LED_POWER") (pin "1") (pinfunction "1_1") (pintype "bidirectional"))
      (node (ref "R2") (pin "2") (pinfunction "P$2_2") (pintype "bidirectional"))
    )
    (net (code "66") (name "Net-(R3-P$1)") (class "Default")
      (node (ref "LED_START") (pin "1") (pinfunction "1_1") (pintype "bidirectional"))
      (node (ref "R3") (pin "1") (pinfunction "P$1_1") (pintype "bidirectional"))
    )
    (net (code "67") (name "Net-(R4-P$1)") (class "Default")
      (node (ref "LED_MOTOR_L1") (pin "2") (pinfunction "2_2") (pintype "bidirectional"))
      (node (ref "LED_MOTOR_L2") (pin "2") (pinfunction "2_2") (pintype "bidirectional"))
      (node (ref "R4") (pin "1") (pinfunction "P$1_1") (pintype "bidirectional"))
    )
    (net (code "68") (name "Net-(R5-P$1)") (class "Default")
      (node (ref "LED_MOTOR_R1") (pin "2") (pinfunction "2_2") (pintype "bidirectional"))
      (node (ref "LED_MOTOR_R2") (pin "2") (pinfunction "2_2") (pintype "bidirectional"))
      (node (ref "R5") (pin "1") (pinfunction "P$1_1") (pintype "bidirectional"))
    )
    (net (code "69") (name "Net-(R9-P$2)") (class "Default")
      (node (ref "LED_RX") (pin "2") (pinfunction "2_2") (pintype "bidirectional"))
      (node (ref "R9") (pin "2") (pinfunction "P$2_2") (pintype "bidirectional"))
    )
    (net (code "70") (name "Net-(R10-P$2)") (class "Default")
      (node (ref "LED_TX") (pin "2") (pinfunction "2_2") (pintype "bidirectional"))
      (node (ref "R10") (pin "2") (pinfunction "P$2_2") (pintype "bidirectional"))
    )
    (net (code "71") (name "Net-(R15-P$1)") (class "Default")
      (node (ref "LED_BT_STAT") (pin "1") (pinfunction "1_1") (pintype "bidirectional"))
      (node (ref "R15") (pin "1") (pinfunction "P$1_1") (pintype "bidirectional"))
    )
    (net (code "72") (name "Net-(R20-P$2)") (class "Default")
      (node (ref "LED_BT_CONN") (pin "2") (pinfunction "2_2") (pintype "bidirectional"))
      (node (ref "R20") (pin "2") (pinfunction "P$2_2") (pintype "bidirectional"))
    )
    (net (code "73") (name "Net-(R29-P$1)") (class "Default")
      (node (ref "R29") (pin "1") (pinfunction "P$1_1") (pintype "bidirectional"))
      (node (ref "WDT1") (pin "10") (pinfunction "~{P0}_10") (pintype "output"))
    )
    (net (code "74") (name "Net-(R29-P$2)") (class "Default")
      (node (ref "C22") (pin "2") (pinfunction "2_2") (pintype "passive"))
      (node (ref "R29") (pin "2") (pinfunction "P$2_2") (pintype "bidirectional"))
      (node (ref "R30") (pin "1") (pinfunction "P$1_1") (pintype "bidirectional"))
    )
    (net (code "75") (name "Net-(R30-P$2)") (class "Default")
      (node (ref "R30") (pin "2") (pinfunction "P$2_2") (pintype "bidirectional"))
      (node (ref "WDT1") (pin "11") (pinfunction "P1_11") (pintype "input"))
    )
    (net (code "76") (name "Net-(R32-P$2)") (class "Default")
      (node (ref "C30") (pin "1") (pinfunction "1_1") (pintype "passive"))
      (node (ref "R32") (pin "2") (pinfunction "P$2_2") (pintype "bidirectional"))
      (node (ref "R33") (pin "2") (pinfunction "P$2_2") (pintype "bidirectional"))
      (node (ref "RST2") (pin "3") (pinfunction "VCC_3") (pintype "bidirectional"))
    )
    (net (code "77") (name "Net-(R36-P$1)") (class "Default")
      (node (ref "C31") (pin "1") (pinfunction "1_1") (pintype "passive"))
      (node (ref "R36") (pin "1") (pinfunction "P$1_1") (pintype "bidirectional"))
      (node (ref "R39") (pin "1") (pinfunction "P$1_1") (pintype "bidirectional"))
      (node (ref "RST3") (pin "3") (pinfunction "VCC_3") (pintype "bidirectional"))
    )
    (net (code "78") (name "Net-(R37-P$1)") (class "Default")
      (node (ref "R37") (pin "1") (pinfunction "P$1_1") (pintype "bidirectional"))
      (node (ref "RST3") (pin "2") (pinfunction "RESET-_2") (pintype "bidirectional"))
    )
    (net (code "79") (name "Net-(R37-P$2)") (class "Default")
      (node (ref "LED_LOW_BATT") (pin "2") (pinfunction "2_2") (pintype "bidirectional"))
      (node (ref "R37") (pin "2") (pinfunction "P$2_2") (pintype "bidirectional"))
    )
    (net (code "80") (name "Net-(TVS1-P$1)") (class "Default")
      (node (ref "TVS1") (pin "1") (pinfunction "P$1_1") (pintype "bidirectional"))
      (node (ref "USB_CONN") (pin "3") (pinfunction "D+_3") (pintype "bidirectional"))
      (node (ref "USB_FILTER") (pin "1") (pinfunction "P$1_1") (pintype "bidirectional"))
    )
    (net (code "81") (name "Net-(TVS1-P$6)") (class "Default")
      (node (ref "TVS1") (pin "6") (pinfunction "P$6_6") (pintype "bidirectional"))
      (node (ref "USB_CONN") (pin "2") (pinfunction "D-_2") (pintype "bidirectional"))
      (node (ref "USB_FILTER") (pin "4") (pinfunction "P$4_4") (pintype "bidirectional"))
    )
    (net (code "82") (name "Net-(WDT1A-P0)") (class "Default")
      (node (ref "C22") (pin "1") (pinfunction "1_1") (pintype "passive"))
      (node (ref "WDT1") (pin "9") (pinfunction "P0_9") (pintype "output"))
    )
    (net (code "83") (name "ON_OFF_BT") (class "Default")
      (node (ref "BUTTON_ON_OFF") (pin "P$1") (pinfunction "4_P$1") (pintype "passive"))
      (node (ref "BUTTON_ON_OFF") (pin "P$3") (pinfunction "3_P$3") (pintype "passive"))
      (node (ref "CTRL1") (pin "5") (pinfunction "PB-_5") (pintype "bidirectional"))
      (node (ref "R35") (pin "1") (pinfunction "P$1_1") (pintype "bidirectional"))
    )
    (net (code "84") (name "PB0") (class "Default")
      (node (ref "IC2") (pin "12") (pinfunction "PB0_12") (pintype "bidirectional"))
      (node (ref "JP5") (pin "5") (pinfunction "5_5") (pintype "passive"))
      (node (ref "R46") (pin "1") (pinfunction "P$1_1") (pintype "bidirectional"))
    )
    (net (code "85") (name "PB1") (class "Default")
      (node (ref "IC2") (pin "13") (pinfunction "PB1_13") (pintype "bidirectional"))
      (node (ref "LED_MOTOR_R1") (pin "1") (pinfunction "1_1") (pintype "bidirectional"))
      (node (ref "MOTOR_CONTROLLER") (pin "4") (pinfunction "IN3_4") (pintype "bidirectional"))
      (node (ref "OR1") (pin "2") (pinfunction "A_2") (pintype "input"))
    )
    (net (code "86") (name "PB2") (class "Default")
      (node (ref "IC2") (pin "14") (pinfunction "PB2_14") (pintype "bidirectional"))
      (node (ref "LED_MOTOR_R2") (pin "1") (pinfunction "1_1") (pintype "bidirectional"))
      (node (ref "MOTOR_CONTROLLER") (pin "5") (pinfunction "IN4_5") (pintype "bidirectional"))
    )
    (net (code "87") (name "PB3") (class "Default")
      (node (ref "IC2") (pin "15") (pinfunction "PB3/MOSI_15") (pintype "bidirectional"))
      (node (ref "JP5") (pin "14") (pinfunction "14_14") (pintype "passive"))
      (node (ref "R53") (pin "1") (pinfunction "P$1_1") (pintype "bidirectional"))
    )
    (net (code "88") (name "PB4") (class "Default")
      (node (ref "IC2") (pin "16") (pinfunction "PB4/MISO_16") (pintype "bidirectional"))
      (node (ref "JP5") (pin "16") (pinfunction "16_16") (pintype "passive"))
      (node (ref "R56") (pin "1") (pinfunction "P$1_1") (pintype "bidirectional"))
    )
    (net (code "89") (name "PB5") (class "Default")
      (node (ref "IC2") (pin "17") (pinfunction "PB5/SCK_17") (pintype "bidirectional"))
      (node (ref "JP5") (pin "18") (pinfunction "18_18") (pintype "passive"))
      (node (ref "R3") (pin "2") (pinfunction "P$2_2") (pintype "bidirectional"))
    )
    (net (code "90") (name "PC0") (class "Default")
      (node (ref "BUTTON_PROG_START") (pin "P$1") (pinfunction "4_P$1") (pintype "passive"))
      (node (ref "BUTTON_PROG_START") (pin "P$3") (pinfunction "3_P$3") (pintype "passive"))
      (node (ref "IC2") (pin "23") (pinfunction "PC0/ADC0_23") (pintype "bidirectional"))
      (node (ref "OR1") (pin "4") (pinfunction "C_4") (pintype "input"))
      (node (ref "R8") (pin "1") (pinfunction "P$1_1") (pintype "bidirectional"))
    )
    (net (code "91") (name "PC1") (class "Default")
      (node (ref "IC2") (pin "24") (pinfunction "PC1/ADC1_24") (pintype "bidirectional"))
      (node (ref "JP5") (pin "2") (pinfunction "2_2") (pintype "passive"))
      (node (ref "R43") (pin "1") (pinfunction "P$1_1") (pintype "bidirectional"))
      (node (ref "R47") (pin "2") (pinfunction "P$2_2") (pintype "bidirectional"))
    )
    (net (code "92") (name "PC2") (class "Default")
      (node (ref "IC2") (pin "25") (pinfunction "PC2/ADC2_25") (pintype "bidirectional"))
      (node (ref "JP5") (pin "4") (pinfunction "4_4") (pintype "passive"))
      (node (ref "R49") (pin "1") (pinfunction "P$1_1") (pintype "bidirectional"))
      (node (ref "R51") (pin "2") (pinfunction "P$2_2") (pintype "bidirectional"))
    )
    (net (code "93") (name "PC3") (class "Default")
      (node (ref "IC2") (pin "26") (pinfunction "PC3/ADC3_26") (pintype "bidirectional"))
      (node (ref "JP5") (pin "6") (pinfunction "6_6") (pintype "passive"))
      (node (ref "R45") (pin "1") (pinfunction "P$1_1") (pintype "bidirectional"))
      (node (ref "R48") (pin "2") (pinfunction "P$2_2") (pintype "bidirectional"))
    )
    (net (code "94") (name "PC4") (class "Default")
      (node (ref "IC2") (pin "27") (pinfunction "PC4/ADC4_27") (pintype "bidirectional"))
      (node (ref "JP5") (pin "8") (pinfunction "8_8") (pintype "passive"))
      (node (ref "R52") (pin "1") (pinfunction "P$1_1") (pintype "bidirectional"))
      (node (ref "R54") (pin "2") (pinfunction "P$2_2") (pintype "bidirectional"))
    )
    (net (code "95") (name "PC5") (class "Default")
      (node (ref "IC2") (pin "28") (pinfunction "PC5/ADC5_28") (pintype "bidirectional"))
      (node (ref "JP5") (pin "10") (pinfunction "10_10") (pintype "passive"))
      (node (ref "R55") (pin "1") (pinfunction "P$1_1") (pintype "bidirectional"))
      (node (ref "R57") (pin "2") (pinfunction "P$2_2") (pintype "bidirectional"))
    )
    (net (code "96") (name "PD0{slash}RXD") (class "Default")
      (node (ref "R14") (pin "2") (pinfunction "P$2_2") (pintype "bidirectional"))
      (node (ref "R16") (pin "2") (pinfunction "P$2_2") (pintype "bidirectional"))
      (node (ref "R6") (pin "2") (pinfunction "P$2_2") (pintype "bidirectional"))
    )
    (net (code "97") (name "PD1{slash}TXD") (class "Default")
      (node (ref "IC1") (pin "5") (pinfunction "RXD_5") (pintype "bidirectional"))
      (node (ref "R11") (pin "2") (pinfunction "P$2_2") (pintype "bidirectional"))
      (node (ref "R17") (pin "2") (pinfunction "P$2_2") (pintype "bidirectional"))
    )
    (net (code "98") (name "PD2") (class "Default")
      (node (ref "IC2") (pin "32") (pinfunction "PD2_32") (pintype "bidirectional"))
      (node (ref "JP5") (pin "13") (pinfunction "13_13") (pintype "passive"))
      (node (ref "S1") (pin "11") (pinfunction "11_11") (pintype "passive"))
    )
    (net (code "99") (name "PD2_DIP") (class "Default")
      (node (ref "INV1") (pin "2") (pinfunction "1Y_2") (pintype "output"))
      (node (ref "R24") (pin "2") (pinfunction "2_2") (pintype "passive"))
      (node (ref "S1") (pin "2") (pinfunction "2_2") (pintype "passive"))
    )
    (net (code "100") (name "PD3") (class "Default")
      (node (ref "IC2") (pin "1") (pinfunction "PD3_1") (pintype "bidirectional"))
      (node (ref "JP5") (pin "15") (pinfunction "15_15") (pintype "passive"))
      (node (ref "S1") (pin "12") (pinfunction "12_12") (pintype "passive"))
    )
    (net (code "101") (name "PD3_DIP") (class "Default")
      (node (ref "INV1") (pin "4") (pinfunction "2Y_4") (pintype "output"))
      (node (ref "R25") (pin "2") (pinfunction "2_2") (pintype "passive"))
      (node (ref "S1") (pin "1") (pinfunction "1_1") (pintype "passive"))
    )
    (net (code "102") (name "PD4") (class "Default")
      (node (ref "IC2") (pin "2") (pinfunction "PD4_2") (pintype "bidirectional"))
      (node (ref "JP5") (pin "1") (pinfunction "1_1") (pintype "passive"))
      (node (ref "R44") (pin "1") (pinfunction "P$1_1") (pintype "bidirectional"))
    )
    (net (code "103") (name "PD5") (class "Default")
      (node (ref "IC2") (pin "9") (pinfunction "PD5_9") (pintype "bidirectional"))
      (node (ref "LED_MOTOR_L1") (pin "1") (pinfunction "1_1") (pintype "bidirectional"))
      (node (ref "MOTOR_CONTROLLER") (pin "2") (pinfunction "IN1_2") (pintype "bidirectional"))
      (node (ref "OR1") (pin "5") (pinfunction "D_5") (pintype "input"))
    )
    (net (code "104") (name "PD6") (class "Default")
      (node (ref "IC2") (pin "10") (pinfunction "PD6_10") (pintype "bidirectional"))
      (node (ref "LED_MOTOR_L2") (pin "1") (pinfunction "1_1") (pintype "bidirectional"))
      (node (ref "MOTOR_CONTROLLER") (pin "3") (pinfunction "IN2_3") (pintype "bidirectional"))
    )
    (net (code "105") (name "PD7") (class "Default")
      (node (ref "IC2") (pin "11") (pinfunction "PD7_11") (pintype "bidirectional"))
      (node (ref "JP5") (pin "3") (pinfunction "3_3") (pintype "passive"))
      (node (ref "R50") (pin "1") (pinfunction "P$1_1") (pintype "bidirectional"))
    )
    (net (code "106") (name "RESET") (class "Default")
      (node (ref "BUTTON_RESET") (pin "P$1") (pinfunction "4_P$1") (pintype "passive"))
      (node (ref "BUTTON_RESET") (pin "P$3") (pinfunction "3_P$3") (pintype "passive"))
      (node (ref "C7") (pin "2") (pinfunction "2_2") (pintype "passive"))
      (node (ref "D3") (pin "3") (pinfunction "C_3") (pintype "passive"))
      (node (ref "IC2") (pin "29") (pinfunction "PC6/RESET_29") (pintype "bidirectional"))
      (node (ref "JP5") (pin "12") (pinfunction "12_12") (pintype "passive"))
      (node (ref "R7") (pin "1") (pinfunction "P$1_1") (pintype "bidirectional"))
      (node (ref "RST1") (pin "2") (pinfunction "RESET-_2") (pintype "bidirectional"))
    )
    (net (code "107") (name "USB_VCC") (class "Default")
      (node (ref "C27") (pin "1") (pinfunction "1_1") (pintype "passive"))
      (node (ref "C5") (pin "1") (pinfunction "1_1") (pintype "passive"))
      (node (ref "D2") (pin "2") (pinfunction "A_2") (pintype "passive"))
      (node (ref "F1") (pin "2A") (pinfunction "2_2A") (pintype "passive"))
      (node (ref "F1") (pin "2B") (pinfunction "2_2B") (pintype "passive"))
      (node (ref "OR1") (pin "9") (pinfunction "E_9") (pintype "input"))
      (node (ref "Q4") (pin "2") (pinfunction "S_2") (pintype "bidirectional"))
      (node (ref "R27") (pin "2") (pinfunction "P$2_2") (pintype "bidirectional"))
      (node (ref "R42") (pin "1") (pinfunction "1_1") (pintype "passive"))
    )
    (net (code "108") (name "VCC") (class "Default")
      (node (ref "3V3REG") (pin "1") (pinfunction "IN_1") (pintype "input"))
      (node (ref "5VREG") (pin "1") (pinfunction "INPUT_1") (pintype "power_in"))
      (node (ref "C1") (pin "1") (pinfunction "1_1") (pintype "passive"))
      (node (ref "C28") (pin "1") (pinfunction "1_1") (pintype "passive"))
      (node (ref "D5") (pin "ANODE") (pinfunction "A_ANODE") (pintype "passive"))
      (node (ref "JP5") (pin "17") (pinfunction "17_17") (pintype "passive"))
      (node (ref "LED_LOW_BATT") (pin "1") (pinfunction "1_1") (pintype "bidirectional"))
      (node (ref "Q3") (pin "3") (pinfunction "D_3") (pintype "bidirectional"))
      (node (ref "R31") (pin "2") (pinfunction "P$2_2") (pintype "bidirectional"))
      (node (ref "R32") (pin "1") (pinfunction "P$1_1") (pintype "bidirectional"))
      (node (ref "R36") (pin "2") (pinfunction "P$2_2") (pintype "bidirectional"))
    )
    (net (code "109") (name "VIN") (class "Default")
      (node (ref "C25") (pin "1") (pinfunction "1_1") (pintype "passive"))
      (node (ref "D4") (pin "ANODE") (pinfunction "A_ANODE") (pintype "passive"))
      (node (ref "F4") (pin "1") (pinfunction "1_1") (pintype "passive"))
      (node (ref "JP5") (pin "21") (pinfunction "21_21") (pintype "passive"))
    )
    (net (code "110") (name "VMOT") (class "Default")
      (node (ref "C10") (pin "2") (pinfunction "2_2") (pintype "passive"))
      (node (ref "C8") (pin "2") (pinfunction "2_2") (pintype "passive"))
      (node (ref "C9") (pin "2") (pinfunction "2_2") (pintype "passive"))
      (node (ref "D5") (pin "CATHODE") (pinfunction "C_CATHODE") (pintype "passive"))
      (node (ref "D6") (pin "CATHODE") (pinfunction "C_CATHODE") (pintype "passive"))
      (node (ref "MOTOR_CONTROLLER") (pin "1") (pinfunction "VCC_1") (pintype "bidirectional"))
    )
    (net (code "111") (name "WD_HEARTBEAT") (class "Default")
      (node (ref "C20") (pin "1") (pinfunction "1_1") (pintype "passive"))
      (node (ref "C23") (pin "2") (pinfunction "2_2") (pintype "passive"))
      (node (ref "R26") (pin "2") (pinfunction "P$2_2") (pintype "bidirectional"))
      (node (ref "WDT1") (pin "12") (pinfunction "RES_12") (pintype "input"))
    )
    (net (code "112") (name "WD_OUT") (class "Default")
      (node (ref "S1") (pin "8") (pinfunction "8_8") (pintype "passive"))
      (node (ref "WDT1") (pin "3") (pinfunction "Q14_3") (pintype "output"))
    )
    (net (code "113") (name "WD_OUT_DIP") (class "Default")
      (node (ref "OR1") (pin "10") (pinfunction "F_10") (pintype "input"))
      (node (ref "R28") (pin "2") (pinfunction "P$2_2") (pintype "bidirectional"))
      (node (ref "S1") (pin "5") (pinfunction "5_5") (pintype "passive"))
    )
    (net (code "114") (name "unconnected-(BT_MODULE-AIO0-Pad30)") (class "Default")
      (node (ref "BT_MODULE") (pin "30") (pinfunction "AIO0_30") (pintype "bidirectional"))
    )
    (net (code "115") (name "unconnected-(BT_MODULE-AIO1-Pad35)") (class "Default")
      (node (ref "BT_MODULE") (pin "35") (pinfunction "AIO1_35") (pintype "bidirectional"))
    )
    (net (code "116") (name "unconnected-(BT_MODULE-GPIO4-Pad22)") (class "Default")
      (node (ref "BT_MODULE") (pin "22") (pinfunction "GPIO4_22") (pintype "bidirectional"))
    )
    (net (code "117") (name "unconnected-(BT_MODULE-GPIO6-Pad3)") (class "Default")
      (node (ref "BT_MODULE") (pin "3") (pinfunction "GPIO6_3") (pintype "bidirectional"))
    )
    (net (code "118") (name "unconnected-(BT_MODULE-GPIO8-Pad31)") (class "Default")
      (node (ref "BT_MODULE") (pin "31") (pinfunction "GPIO8_31") (pintype "bidirectional"))
    )
    (net (code "119") (name "unconnected-(BT_MODULE-GPIO9-Pad32)") (class "Default")
      (node (ref "BT_MODULE") (pin "32") (pinfunction "GPIO9_32") (pintype "bidirectional"))
    )
    (net (code "120") (name "unconnected-(BT_MODULE-GPIO10-Pad33)") (class "Default")
      (node (ref "BT_MODULE") (pin "33") (pinfunction "GPIO10_33") (pintype "bidirectional"))
    )
    (net (code "121") (name "unconnected-(BT_MODULE-GPIO11-Pad34)") (class "Default")
      (node (ref "BT_MODULE") (pin "34") (pinfunction "GPIO11_34") (pintype "bidirectional"))
    )
    (net (code "122") (name "unconnected-(BT_MODULE-PCM_CLK-Pad7)") (class "Default")
      (node (ref "BT_MODULE") (pin "7") (pinfunction "PCM_CLK_7") (pintype "bidirectional"))
    )
    (net (code "123") (name "unconnected-(BT_MODULE-PCM_IN-Pad9)") (class "Default")
      (node (ref "BT_MODULE") (pin "9") (pinfunction "PCM_IN_9") (pintype "bidirectional"))
    )
    (net (code "124") (name "unconnected-(BT_MODULE-PCM_OUT-Pad10)") (class "Default")
      (node (ref "BT_MODULE") (pin "10") (pinfunction "PCM_OUT_10") (pintype "bidirectional"))
    )
    (net (code "125") (name "unconnected-(BT_MODULE-PCM_SYNC-Pad8)") (class "Default")
      (node (ref "BT_MODULE") (pin "8") (pinfunction "PCM_SYNC_8") (pintype "bidirectional"))
    )
    (net (code "126") (name "unconnected-(BT_MODULE-SPI_CLK-Pad6)") (class "Default")
      (node (ref "BT_MODULE") (pin "6") (pinfunction "SPI_CLK_6") (pintype "bidirectional"))
    )
    (net (code "127") (name "unconnected-(BT_MODULE-SPI_CSB-Pad23)") (class "Default")
      (node (ref "BT_MODULE") (pin "23") (pinfunction "SPI_CSB_23") (pintype "bidirectional"))
    )
    (net (code "128") (name "unconnected-(BT_MODULE-SPI_MISO-Pad24)") (class "Default")
      (node (ref "BT_MODULE") (pin "24") (pinfunction "SPI_MISO_24") (pintype "bidirectional"))
    )
    (net (code "129") (name "unconnected-(BT_MODULE-SPI_MOSI-Pad2)") (class "Default")
      (node (ref "BT_MODULE") (pin "2") (pinfunction "SPI_MOSI_2") (pintype "bidirectional"))
    )
    (net (code "130") (name "unconnected-(BT_MODULE-USB_D+-Pad17)") (class "Default")
      (node (ref "BT_MODULE") (pin "17") (pinfunction "USB_D+_17") (pintype "bidirectional"))
    )
    (net (code "131") (name "unconnected-(BT_MODULE-USB_D--Pad18)") (class "Default")
      (node (ref "BT_MODULE") (pin "18") (pinfunction "USB_D-_18") (pintype "bidirectional"))
    )
    (net (code "132") (name "unconnected-(CTRL1-INT--Pad8)") (class "Default")
      (node (ref "CTRL1") (pin "8") (pinfunction "INT-_8") (pintype "bidirectional"))
    )
    (net (code "133") (name "unconnected-(CTRL1-TMR-Pad3)") (class "Default")
      (node (ref "CTRL1") (pin "3") (pinfunction "TMR_3") (pintype "bidirectional"))
    )
    (net (code "134") (name "unconnected-(IC1-CBUS2-Pad13)") (class "Default")
      (node (ref "IC1") (pin "13") (pinfunction "CBUS2_13") (pintype "bidirectional"))
    )
    (net (code "135") (name "unconnected-(IC1-CBUS3-Pad14)") (class "Default")
      (node (ref "IC1") (pin "14") (pinfunction "CBUS3_14") (pintype "bidirectional"))
    )
    (net (code "136") (name "unconnected-(IC1-CBUS4-Pad12)") (class "Default")
      (node (ref "IC1") (pin "12") (pinfunction "CBUS4_12") (pintype "bidirectional"))
    )
    (net (code "137") (name "unconnected-(IC1-CTS-Pad11)") (class "Default")
      (node (ref "IC1") (pin "11") (pinfunction "CTS_11") (pintype "bidirectional"))
    )
    (net (code "138") (name "unconnected-(IC1-DCD-Pad10)") (class "Default")
      (node (ref "IC1") (pin "10") (pinfunction "DCD_10") (pintype "bidirectional"))
    )
    (net (code "139") (name "unconnected-(IC1-DSR-Pad9)") (class "Default")
      (node (ref "IC1") (pin "9") (pinfunction "DSR_9") (pintype "bidirectional"))
    )
    (net (code "140") (name "unconnected-(IC1-NC1-Pad8)") (class "Default")
      (node (ref "IC1") (pin "8") (pinfunction "NC1_8") (pintype "bidirectional"))
    )
    (net (code "141") (name "unconnected-(IC1-NC2-Pad24)") (class "Default")
      (node (ref "IC1") (pin "24") (pinfunction "NC2_24") (pintype "bidirectional"))
    )
    (net (code "142") (name "unconnected-(IC1-OSCI-Pad27)") (class "Default")
      (node (ref "IC1") (pin "27") (pinfunction "OSCI_27") (pintype "bidirectional"))
    )
    (net (code "143") (name "unconnected-(IC1-OSCO-Pad28)") (class "Default")
      (node (ref "IC1") (pin "28") (pinfunction "OSCO_28") (pintype "bidirectional"))
    )
    (net (code "144") (name "unconnected-(IC1-RI-Pad6)") (class "Default")
      (node (ref "IC1") (pin "6") (pinfunction "RI_6") (pintype "bidirectional"))
    )
    (net (code "145") (name "unconnected-(IC1-RTS-Pad3)") (class "Default")
      (node (ref "IC1") (pin "3") (pinfunction "RTS_3") (pintype "bidirectional"))
    )
    (net (code "146") (name "unconnected-(INV1-4Y-Pad8)") (class "Default")
      (node (ref "INV1") (pin "8") (pinfunction "4Y_8") (pintype "output"))
    )
    (net (code "147") (name "unconnected-(INV1-5Y-Pad10)") (class "Default")
      (node (ref "INV1") (pin "10") (pinfunction "5Y_10") (pintype "output"))
    )
    (net (code "148") (name "unconnected-(INV1-6Y-Pad12)") (class "Default")
      (node (ref "INV1") (pin "12") (pinfunction "6Y_12") (pintype "output"))
    )
    (net (code "149") (name "unconnected-(OR1-NC-Pad8)") (class "Default")
      (node (ref "OR1") (pin "8") (pinfunction "NC_8") (pintype "no_connect"))
    )
    (net (code "150") (name "unconnected-(OR1-NC_2-Pad6)") (class "Default")
      (node (ref "OR1") (pin "6") (pinfunction "NC_2_6") (pintype "no_connect"))
    )
    (net (code "151") (name "unconnected-(POT1-CW-Pad3)") (class "Default")
      (node (ref "POT1") (pin "3") (pinfunction "CW_3") (pintype "bidirectional"))
    )
    (net (code "152") (name "unconnected-(POT2-CW-Pad3)") (class "Default")
      (node (ref "POT2") (pin "3") (pinfunction "CW_3") (pintype "bidirectional"))
    )
    (net (code "153") (name "unconnected-(S1-Pad6)") (class "Default")
      (node (ref "S1") (pin "6") (pinfunction "6_6") (pintype "passive"))
    )
    (net (code "154") (name "unconnected-(S1-Pad7)") (class "Default")
      (node (ref "S1") (pin "7") (pinfunction "7_7") (pintype "passive"))
    )
    (net (code "155") (name "unconnected-(TVS1-P$4-Pad4)") (class "Default")
      (node (ref "TVS1") (pin "4") (pinfunction "P$4_4") (pintype "bidirectional"))
    )
    (net (code "156") (name "unconnected-(USB_CONN-ID-Pad4)") (class "Default")
      (node (ref "USB_CONN") (pin "4") (pinfunction "ID_4") (pintype "bidirectional"))
    )
    (net (code "157") (name "unconnected-(WDT1A-Q4-Pad7)") (class "Default")
      (node (ref "WDT1") (pin "7") (pinfunction "Q4_7") (pintype "output"))
    )
    (net (code "158") (name "unconnected-(WDT1A-Q5-Pad5)") (class "Default")
      (node (ref "WDT1") (pin "5") (pinfunction "Q5_5") (pintype "output"))
    )
    (net (code "159") (name "unconnected-(WDT1A-Q6-Pad4)") (class "Default")
      (node (ref "WDT1") (pin "4") (pinfunction "Q6_4") (pintype "output"))
    )
    (net (code "160") (name "unconnected-(WDT1A-Q7-Pad6)") (class "Default")
      (node (ref "WDT1") (pin "6") (pinfunction "Q7_6") (pintype "output"))
    )
    (net (code "161") (name "unconnected-(WDT1A-Q8-Pad14)") (class "Default")
      (node (ref "WDT1") (pin "14") (pinfunction "Q8_14") (pintype "output"))
    )
    (net (code "162") (name "unconnected-(WDT1A-Q9-Pad13)") (class "Default")
      (node (ref "WDT1") (pin "13") (pinfunction "Q9_13") (pintype "output"))
    )
    (net (code "163") (name "unconnected-(WDT1A-Q10-Pad15)") (class "Default")
      (node (ref "WDT1") (pin "15") (pinfunction "Q10_15") (pintype "output"))
    )
    (net (code "164") (name "unconnected-(WDT1A-Q12-Pad1)") (class "Default")
      (node (ref "WDT1") (pin "1") (pinfunction "Q12_1") (pintype "output"))
    )
    (net (code "165") (name "unconnected-(WDT1A-Q13-Pad2)") (class "Default")
      (node (ref "WDT1") (pin "2") (pinfunction "Q13_2") (pintype "output"))
    )
  )
)
